# PCB-CCU-IRISCTRL.net
KiCad netlist of a schematic drawn in EAGLE
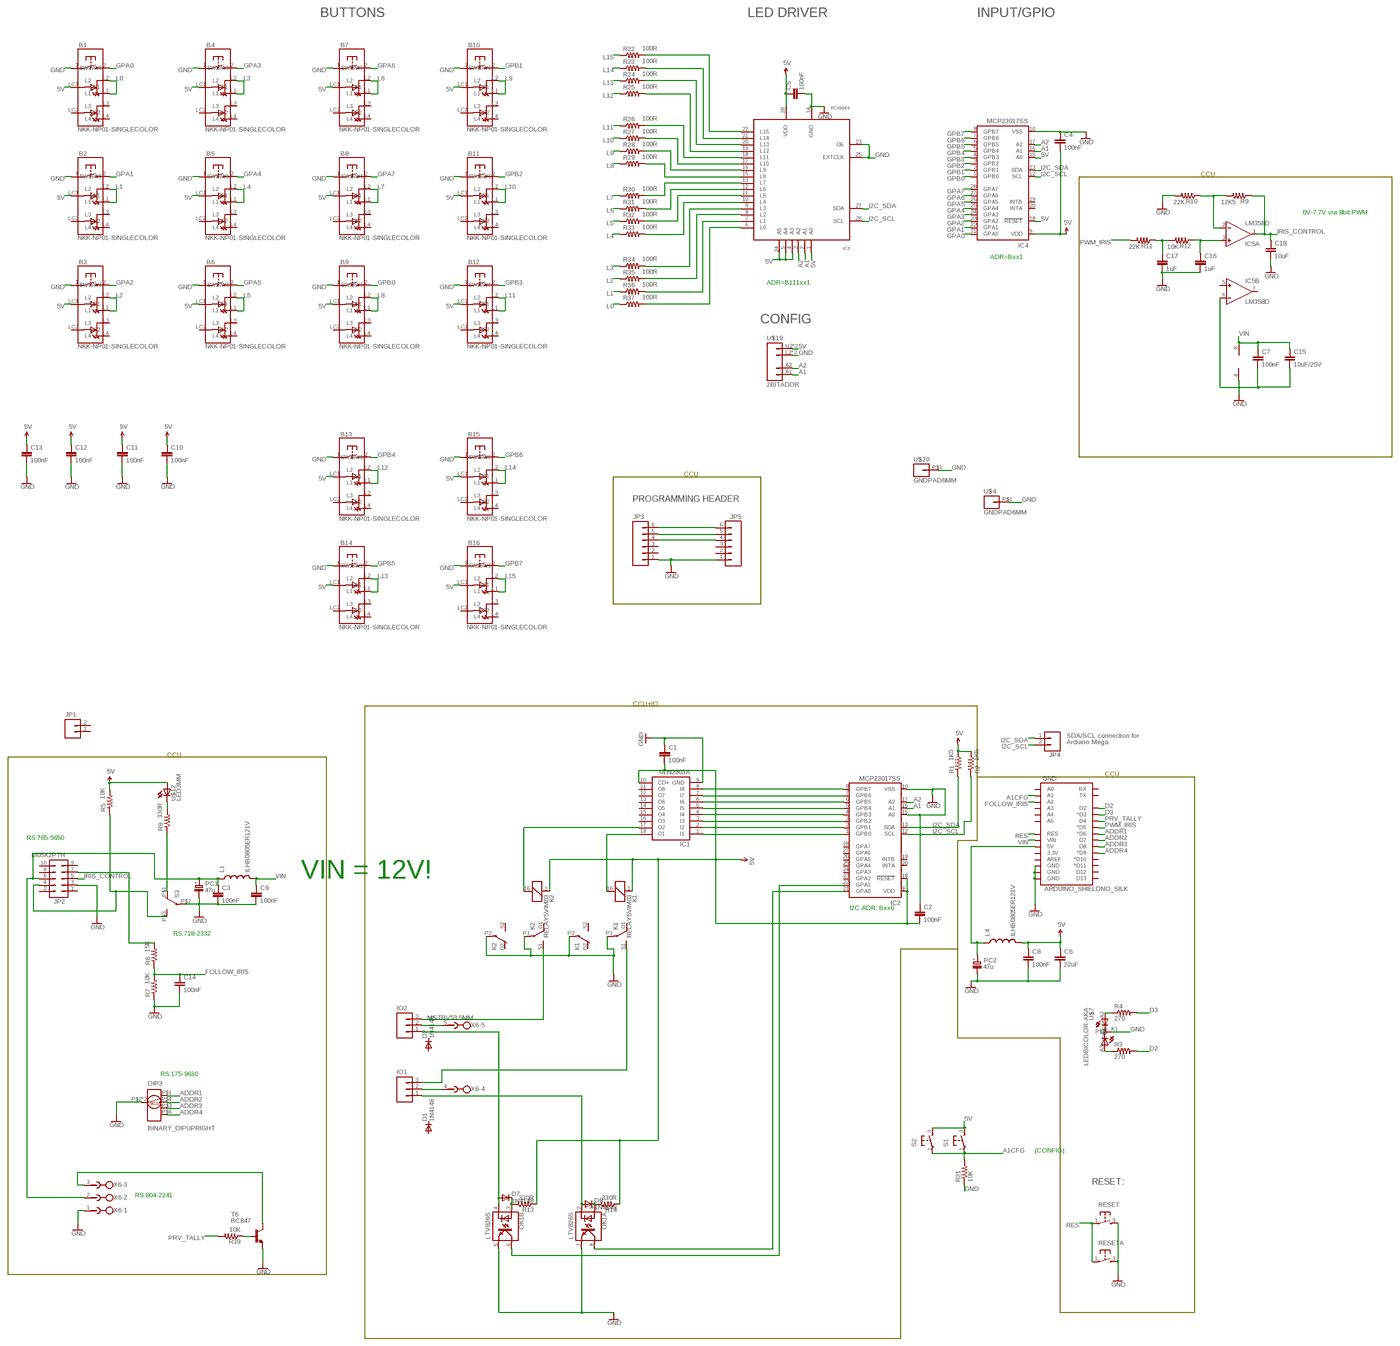
[diagram p0: schematic, sheet 1, overview]
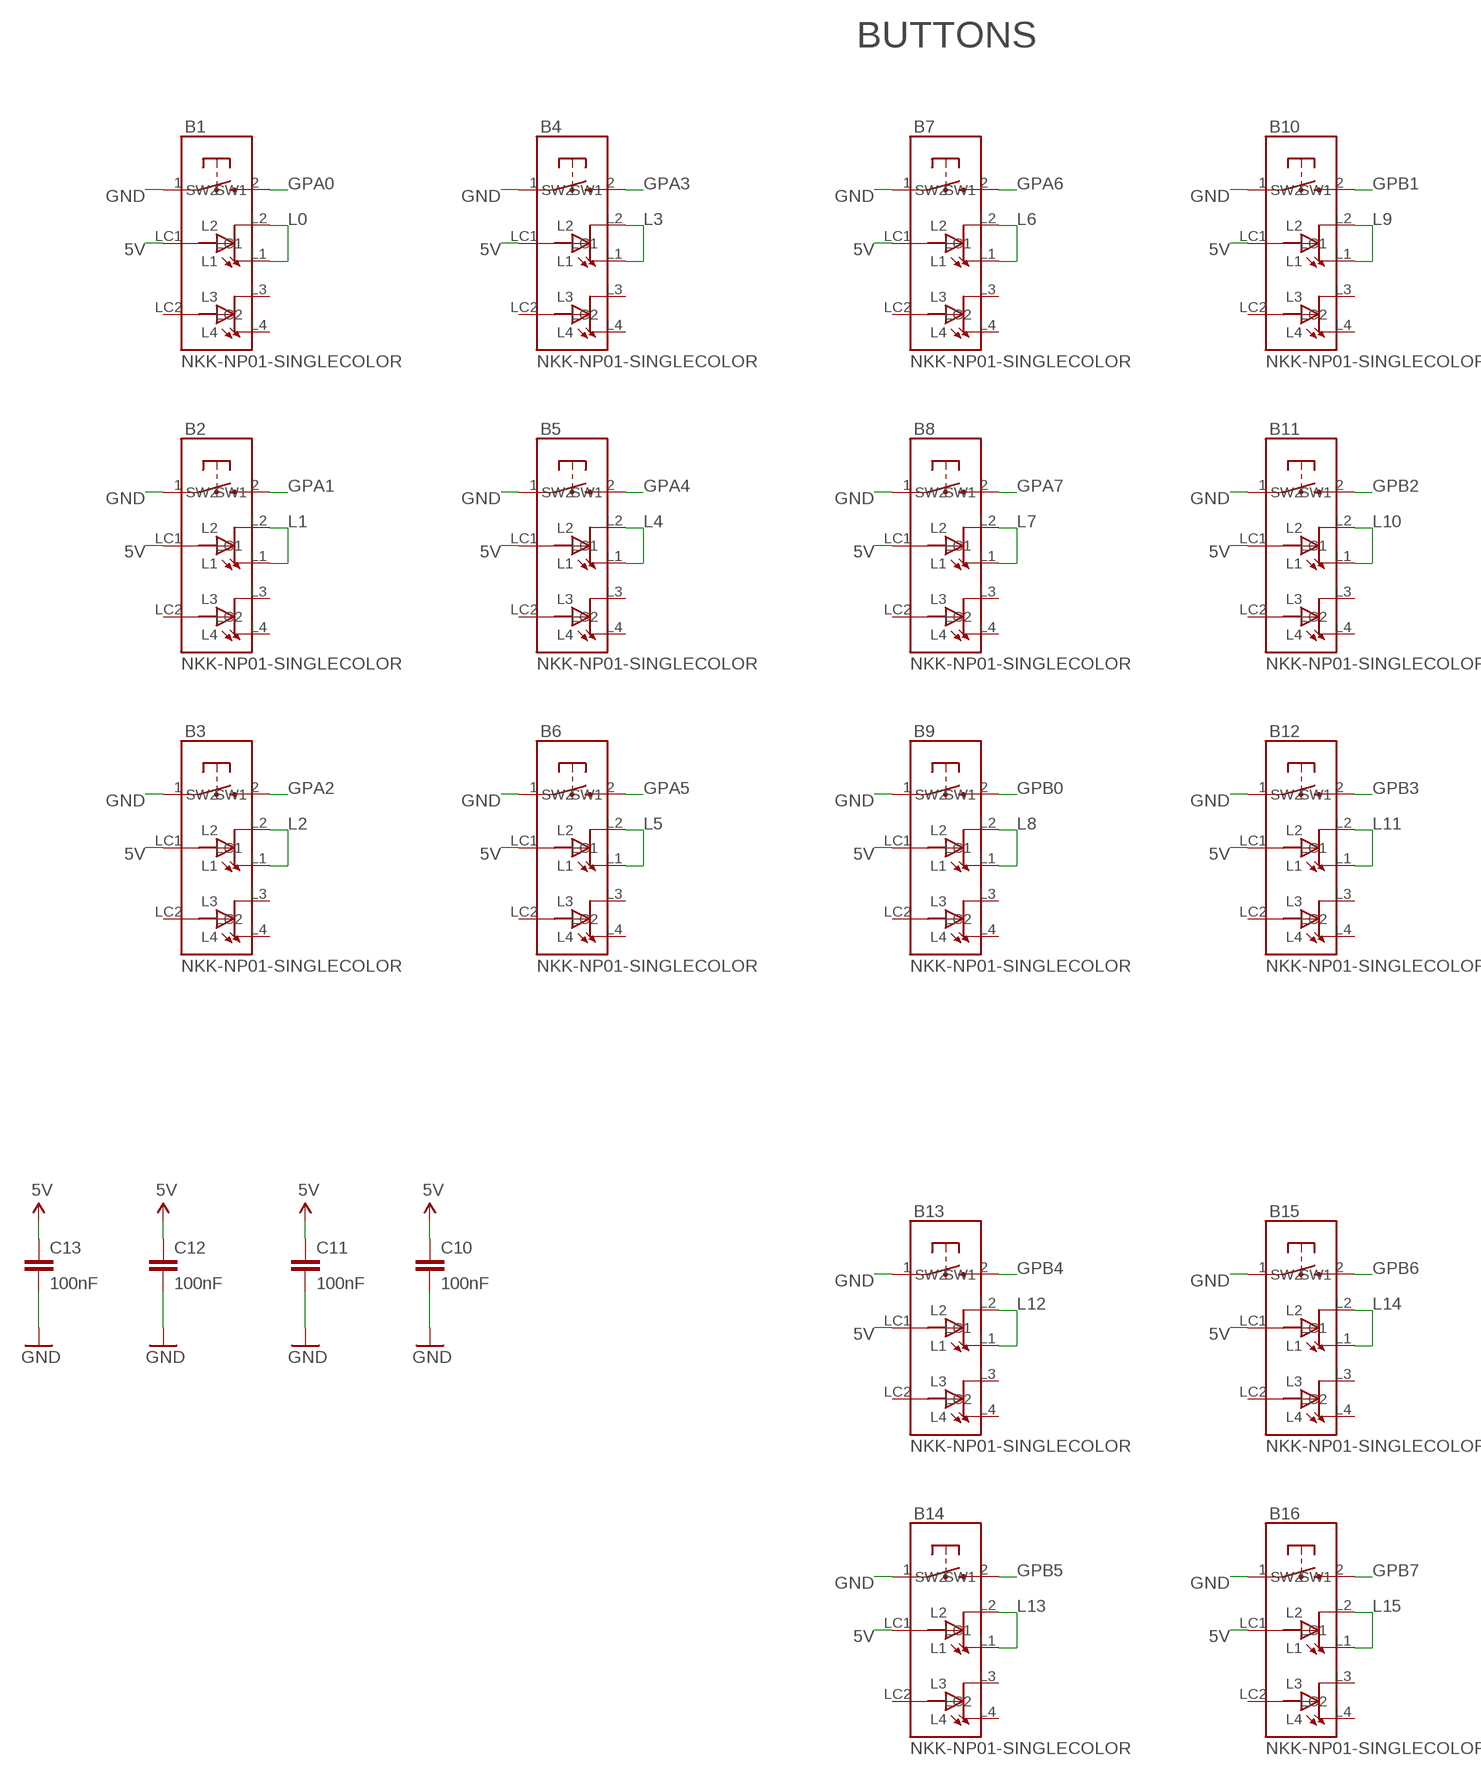
[diagram p1: schematic, sheet 1, part 1 of 4]
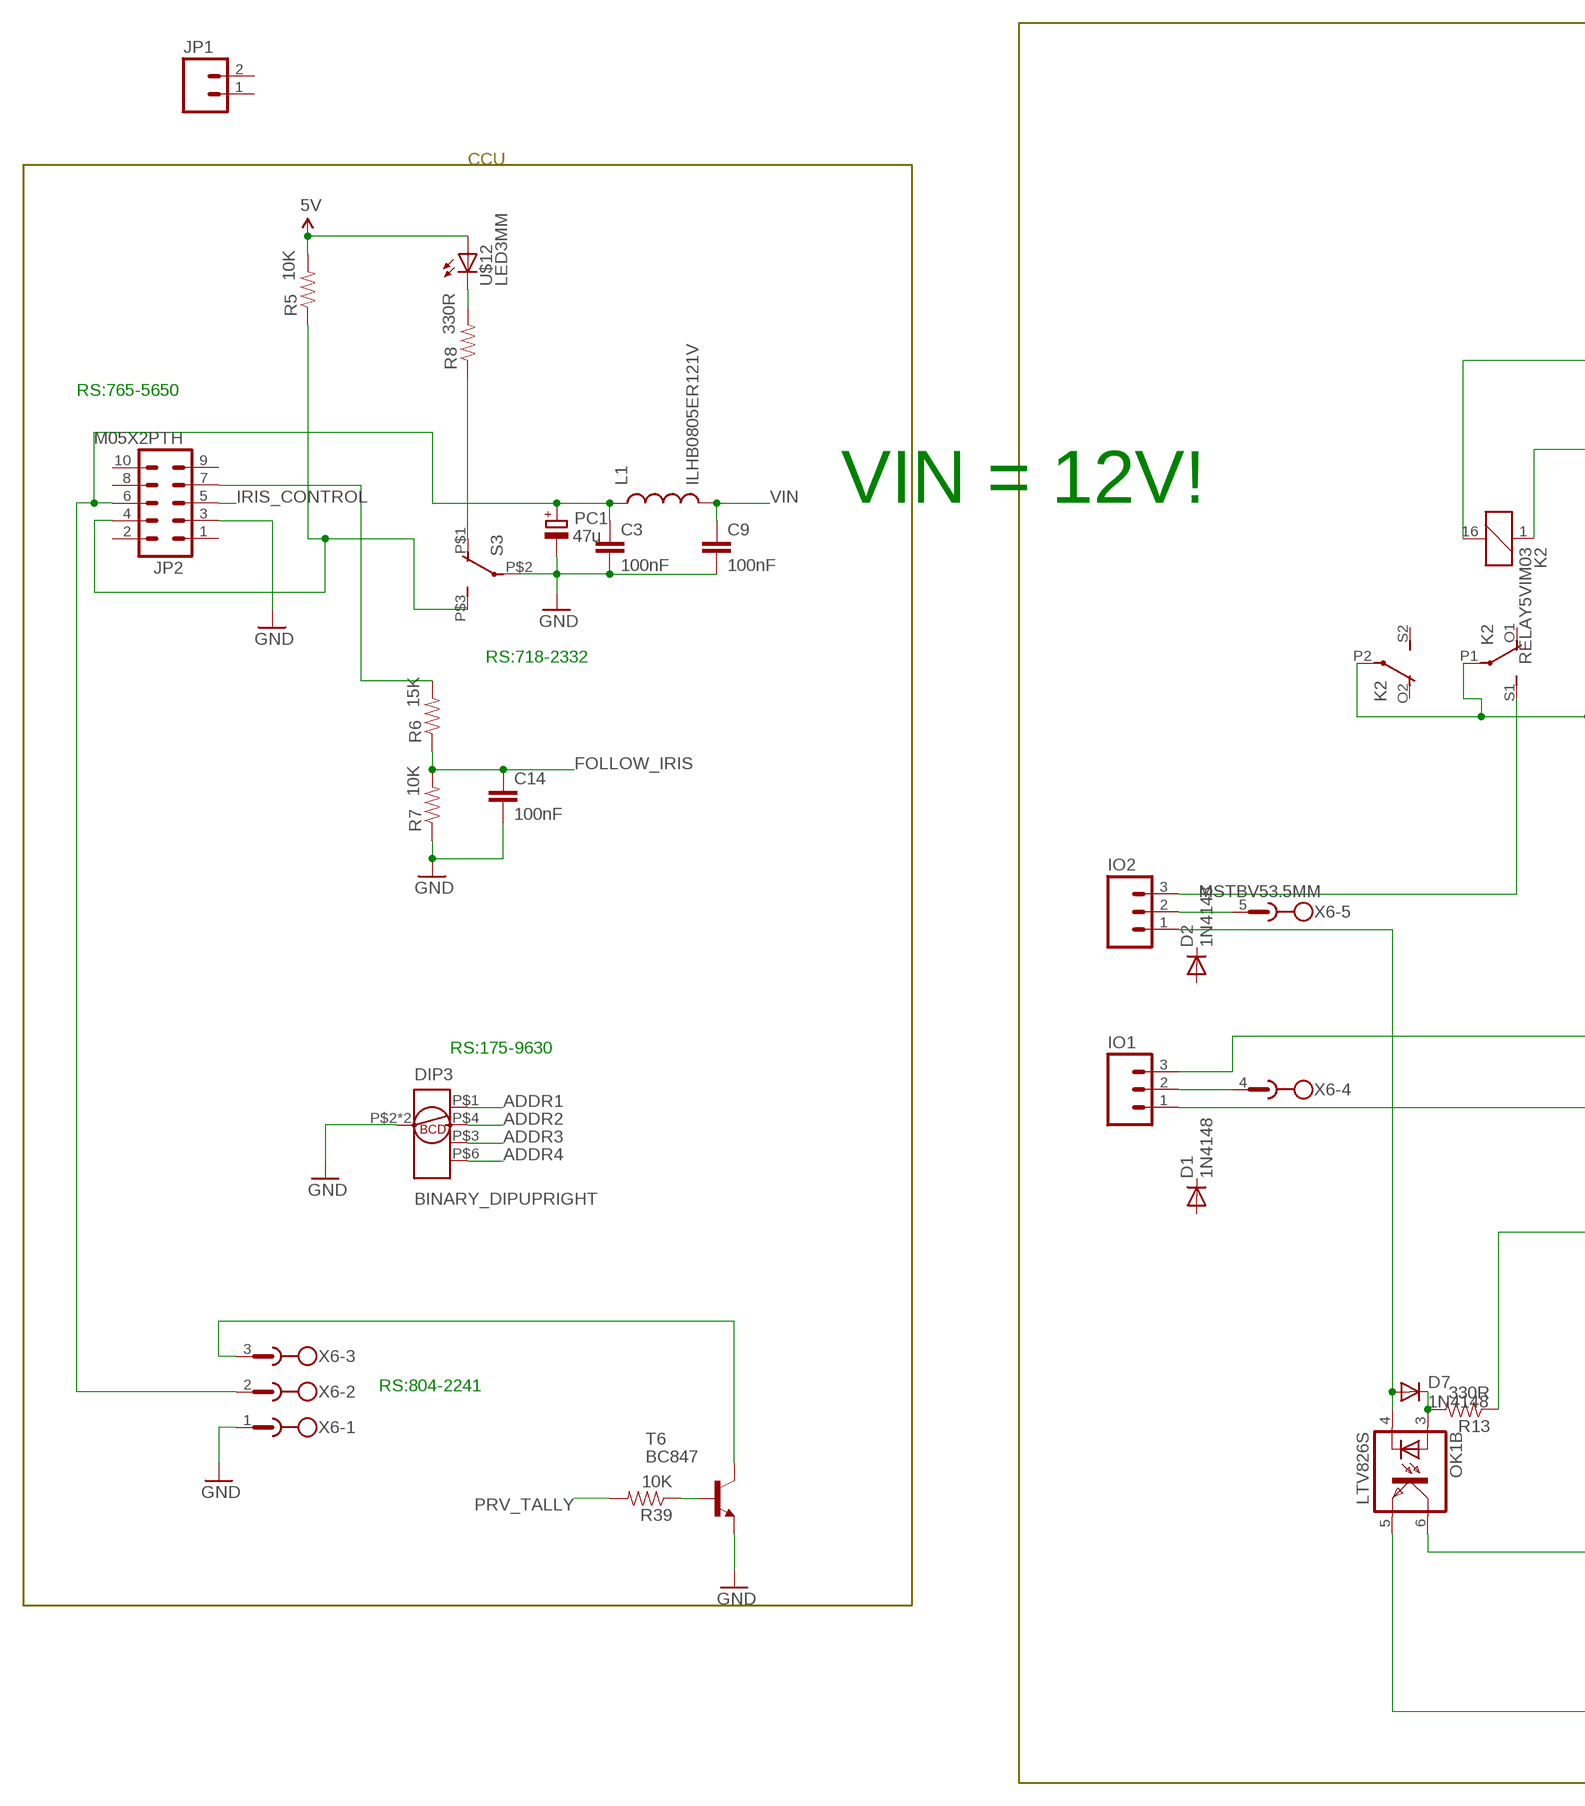
[diagram p2: schematic, sheet 1, part 2 of 4]
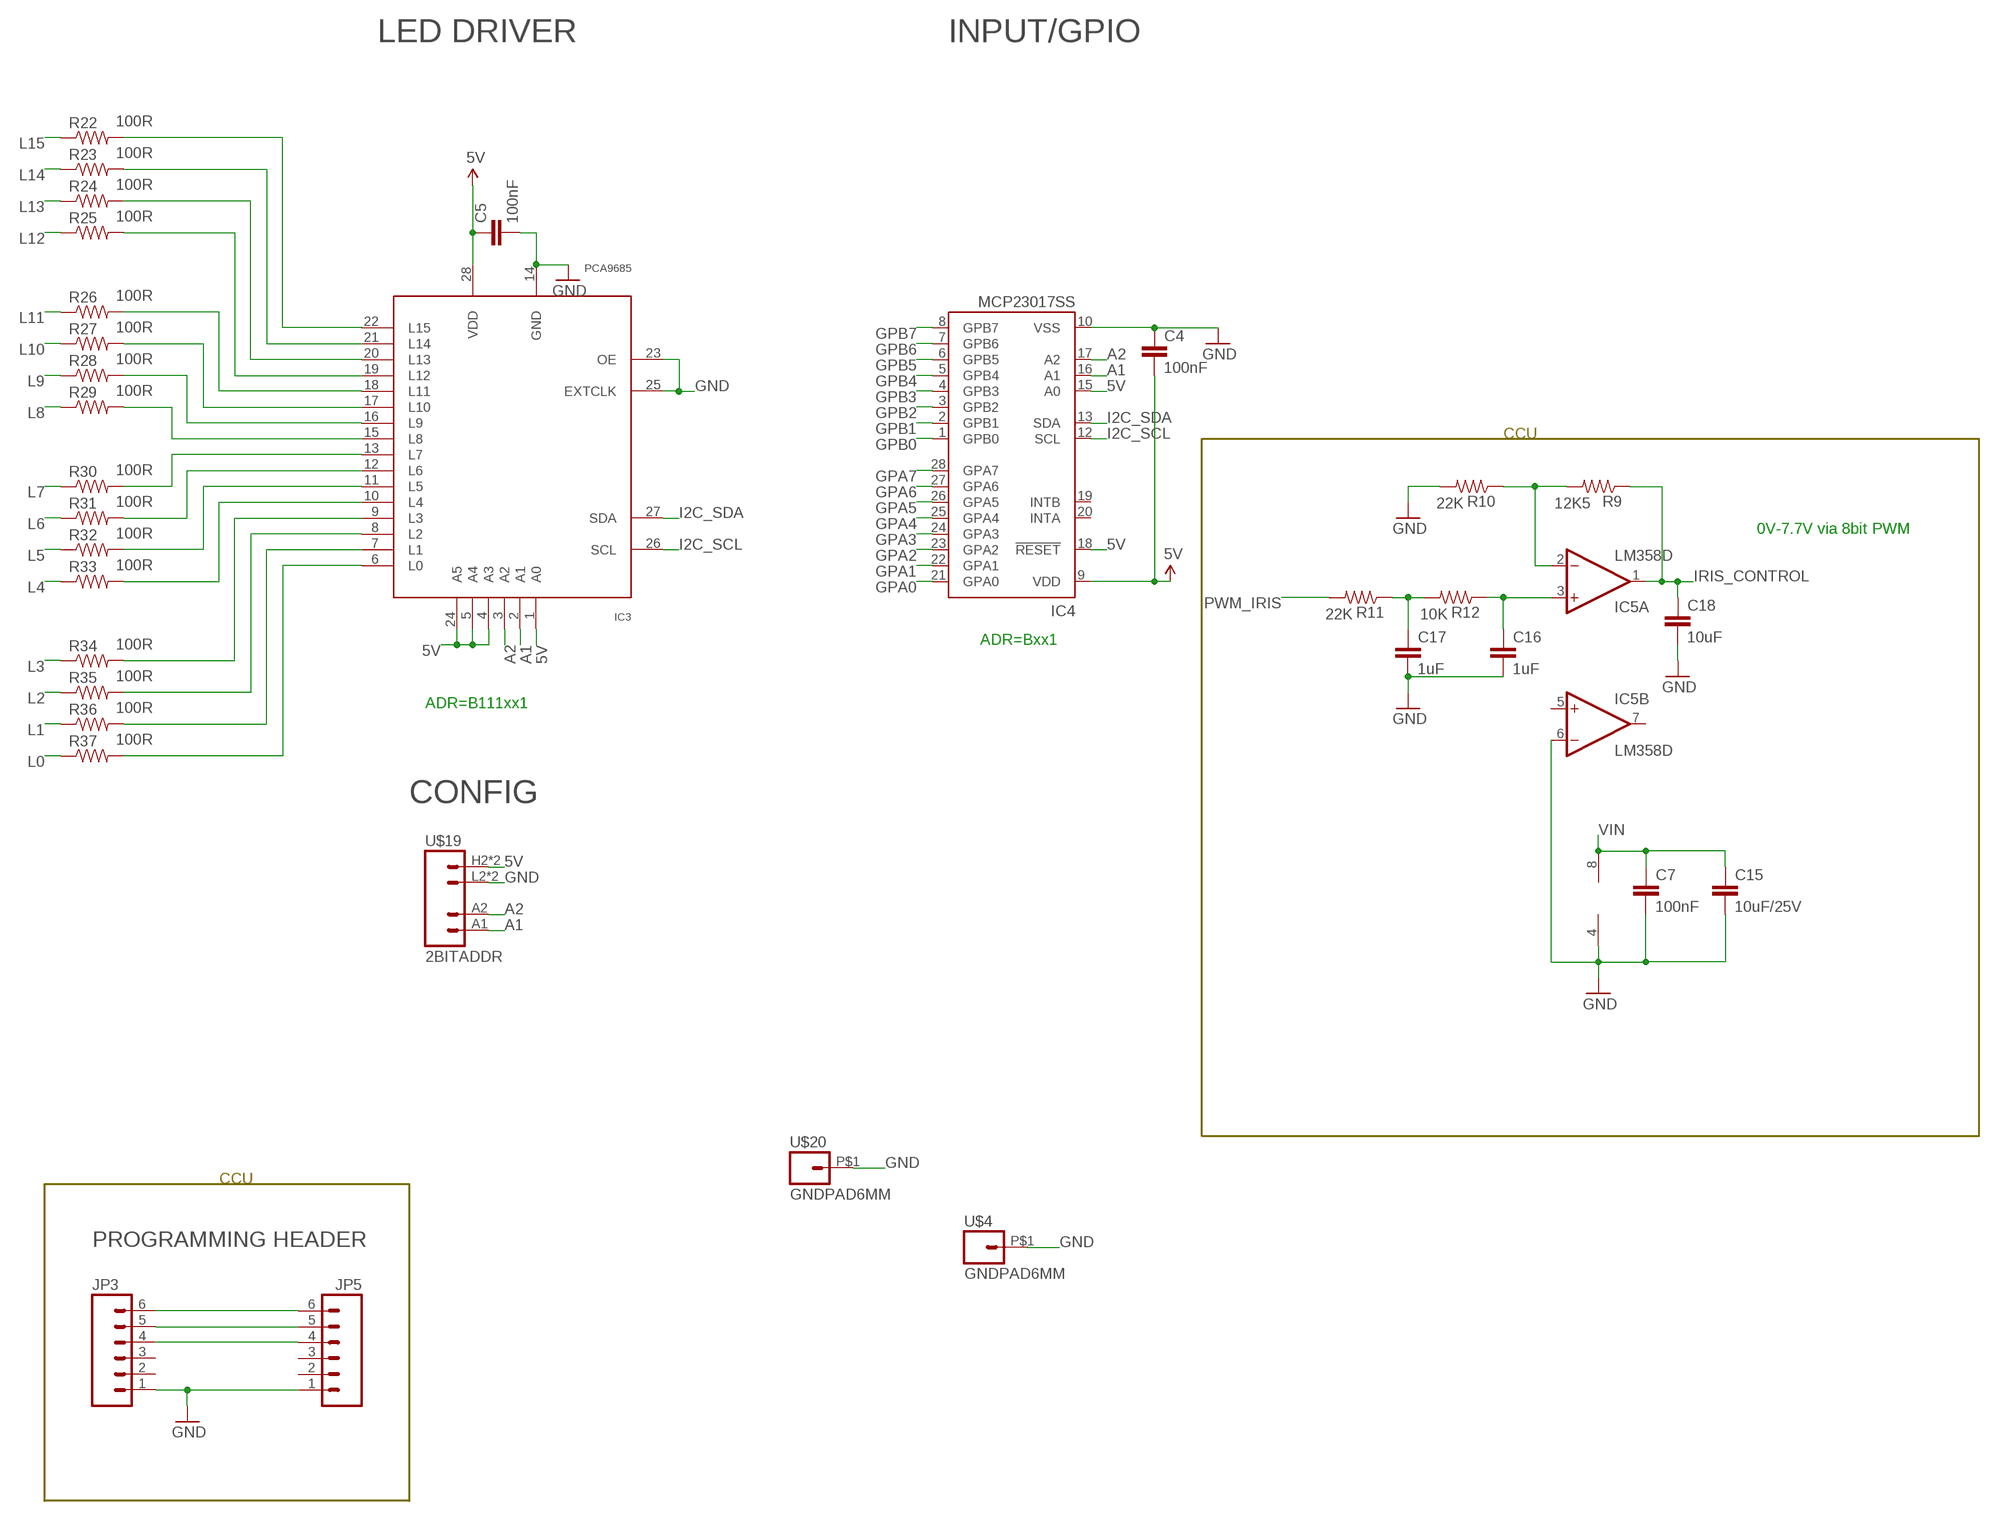
[diagram p3: schematic, sheet 1, part 3 of 4]
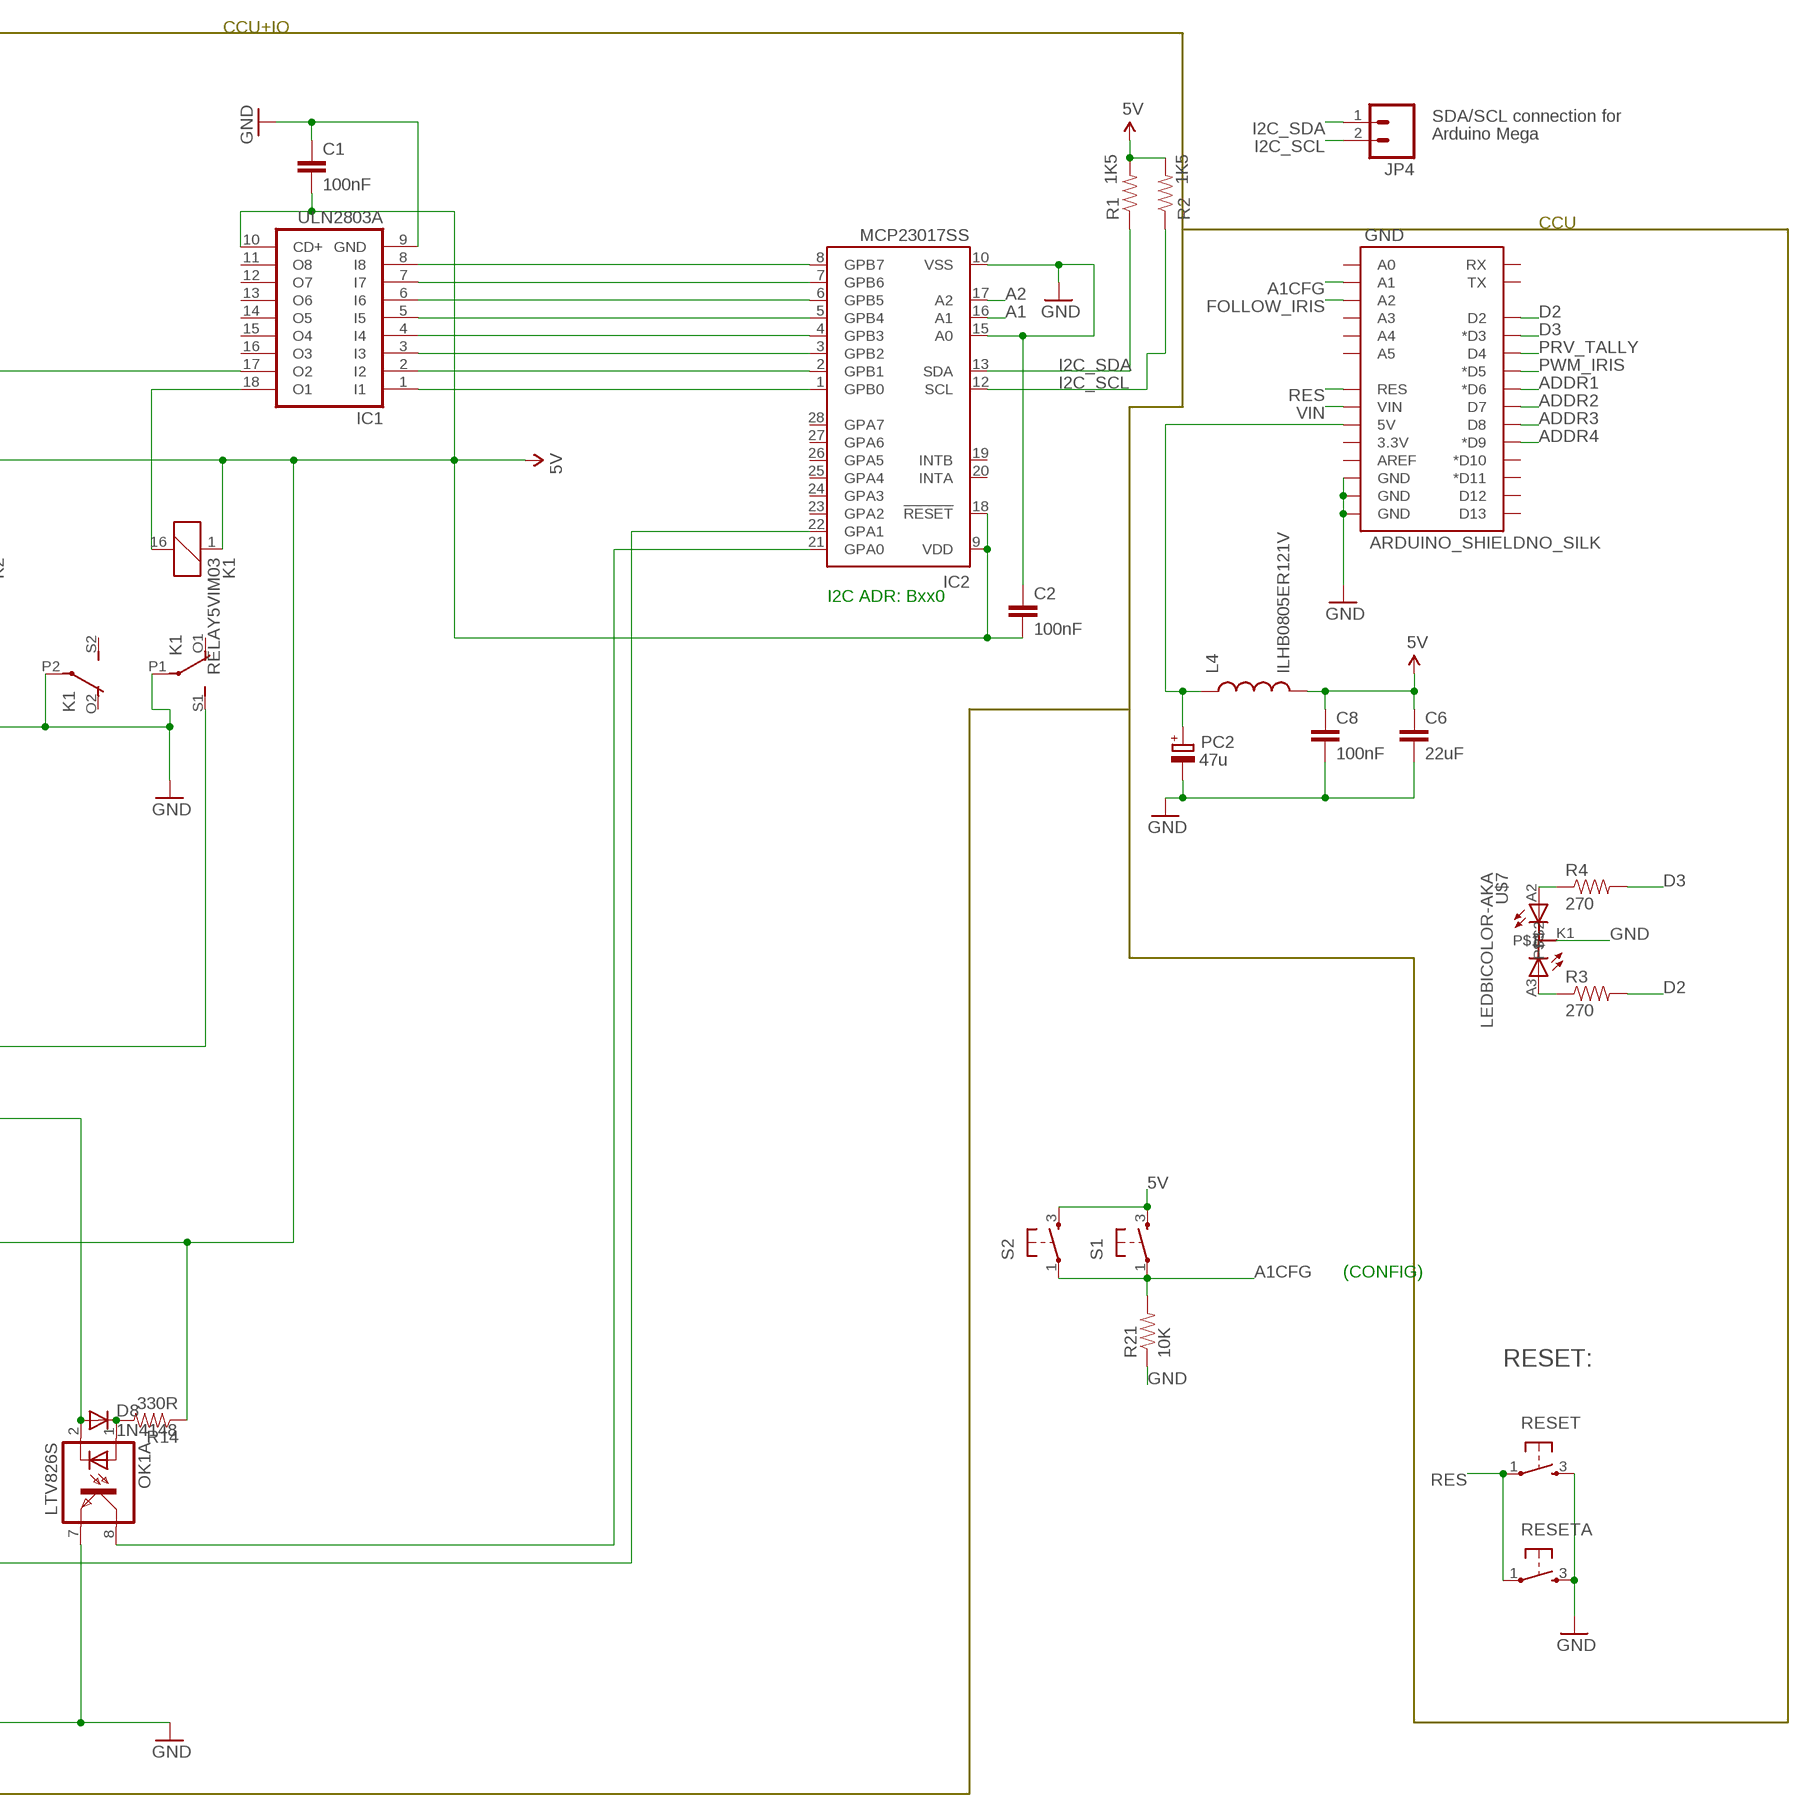
[diagram p4: schematic, sheet 1, part 4 of 4]

(export (version "E")
  (design (tool "Eeschema 10.0.6"))
  (components
    (comp (ref "B1")
      (value "NKK-NP01-SINGLECOLOR")
      (footprint "eagle-import:NKK-NP01")
      (libsource (lib "eagle-import") (part "NKK-NP01-SINGLECOLOR"))
    )
    (comp (ref "B2")
      (value "NKK-NP01-SINGLECOLOR")
      (footprint "eagle-import:NKK-NP01")
      (libsource (lib "eagle-import") (part "NKK-NP01-SINGLECOLOR"))
    )
    (comp (ref "B3")
      (value "NKK-NP01-SINGLECOLOR")
      (footprint "eagle-import:NKK-NP01")
      (libsource (lib "eagle-import") (part "NKK-NP01-SINGLECOLOR"))
    )
    (comp (ref "B4")
      (value "NKK-NP01-SINGLECOLOR")
      (footprint "eagle-import:NKK-NP01")
      (libsource (lib "eagle-import") (part "NKK-NP01-SINGLECOLOR"))
    )
    (comp (ref "B5")
      (value "NKK-NP01-SINGLECOLOR")
      (footprint "eagle-import:NKK-NP01")
      (libsource (lib "eagle-import") (part "NKK-NP01-SINGLECOLOR"))
    )
    (comp (ref "B6")
      (value "NKK-NP01-SINGLECOLOR")
      (footprint "eagle-import:NKK-NP01")
      (libsource (lib "eagle-import") (part "NKK-NP01-SINGLECOLOR"))
    )
    (comp (ref "B7")
      (value "NKK-NP01-SINGLECOLOR")
      (footprint "eagle-import:NKK-NP01")
      (libsource (lib "eagle-import") (part "NKK-NP01-SINGLECOLOR"))
    )
    (comp (ref "B8")
      (value "NKK-NP01-SINGLECOLOR")
      (footprint "eagle-import:NKK-NP01")
      (libsource (lib "eagle-import") (part "NKK-NP01-SINGLECOLOR"))
    )
    (comp (ref "B9")
      (value "NKK-NP01-SINGLECOLOR")
      (footprint "eagle-import:NKK-NP01")
      (libsource (lib "eagle-import") (part "NKK-NP01-SINGLECOLOR"))
    )
    (comp (ref "B10")
      (value "NKK-NP01-SINGLECOLOR")
      (footprint "eagle-import:NKK-NP01")
      (libsource (lib "eagle-import") (part "NKK-NP01-SINGLECOLOR"))
    )
    (comp (ref "B11")
      (value "NKK-NP01-SINGLECOLOR")
      (footprint "eagle-import:NKK-NP01")
      (libsource (lib "eagle-import") (part "NKK-NP01-SINGLECOLOR"))
    )
    (comp (ref "B12")
      (value "NKK-NP01-SINGLECOLOR")
      (footprint "eagle-import:NKK-NP01")
      (libsource (lib "eagle-import") (part "NKK-NP01-SINGLECOLOR"))
    )
    (comp (ref "B13")
      (value "NKK-NP01-SINGLECOLOR")
      (footprint "eagle-import:NKK-NP01")
      (libsource (lib "eagle-import") (part "NKK-NP01-SINGLECOLOR"))
    )
    (comp (ref "B14")
      (value "NKK-NP01-SINGLECOLOR")
      (footprint "eagle-import:NKK-NP01")
      (libsource (lib "eagle-import") (part "NKK-NP01-SINGLECOLOR"))
    )
    (comp (ref "B15")
      (value "NKK-NP01-SINGLECOLOR")
      (footprint "eagle-import:NKK-NP01")
      (libsource (lib "eagle-import") (part "NKK-NP01-SINGLECOLOR"))
    )
    (comp (ref "B16")
      (value "NKK-NP01-SINGLECOLOR")
      (footprint "eagle-import:NKK-NP01")
      (libsource (lib "eagle-import") (part "NKK-NP01-SINGLECOLOR"))
    )
    (comp (ref "C1")
      (value "100nF")
      (footprint "eagle-import:0805")
      (libsource (lib "eagle-import") (part "CAP0805"))
    )
    (comp (ref "C2")
      (value "100nF")
      (footprint "eagle-import:0603-CAP")
      (libsource (lib "eagle-import") (part "CAP0603-CAP"))
    )
    (comp (ref "C3")
      (value "100nF")
      (footprint "eagle-import:0603-CAP")
      (libsource (lib "eagle-import") (part "CAP0603-CAP"))
    )
    (comp (ref "C4")
      (value "100nF")
      (footprint "eagle-import:0603-CAP")
      (libsource (lib "eagle-import") (part "CAP0603-CAP"))
    )
    (comp (ref "C5")
      (value "100nF")
      (footprint "eagle-import:0603-CAP")
      (libsource (lib "eagle-import") (part "CAP0603-CAP"))
    )
    (comp (ref "C6")
      (value "22uF")
      (footprint "eagle-import:0805")
      (libsource (lib "eagle-import") (part "CAP0805"))
    )
    (comp (ref "C7")
      (value "100nF")
      (footprint "eagle-import:0603-CAP")
      (libsource (lib "eagle-import") (part "CAP0603-CAP"))
    )
    (comp (ref "C8")
      (value "100nF")
      (footprint "eagle-import:0603-CAP")
      (libsource (lib "eagle-import") (part "CAP0603-CAP"))
    )
    (comp (ref "C9")
      (value "100nF")
      (footprint "eagle-import:0603-CAP")
      (libsource (lib "eagle-import") (part "CAP0603-CAP"))
    )
    (comp (ref "C10")
      (value "100nF")
      (footprint "eagle-import:0603-CAP")
      (libsource (lib "eagle-import") (part "CAP0603-CAP"))
    )
    (comp (ref "C11")
      (value "100nF")
      (footprint "eagle-import:0603-CAP")
      (libsource (lib "eagle-import") (part "CAP0603-CAP"))
    )
    (comp (ref "C12")
      (value "100nF")
      (footprint "eagle-import:0603-CAP")
      (libsource (lib "eagle-import") (part "CAP0603-CAP"))
    )
    (comp (ref "C13")
      (value "100nF")
      (footprint "eagle-import:0603-CAP")
      (libsource (lib "eagle-import") (part "CAP0603-CAP"))
    )
    (comp (ref "C14")
      (value "100nF")
      (footprint "eagle-import:0603-CAP")
      (libsource (lib "eagle-import") (part "CAP0603-CAP"))
    )
    (comp (ref "C15")
      (value "10uF/25V")
      (footprint "eagle-import:0805")
      (libsource (lib "eagle-import") (part "CAP0805"))
    )
    (comp (ref "C16")
      (value "1uF")
      (footprint "eagle-import:0805")
      (libsource (lib "eagle-import") (part "CAP0805"))
    )
    (comp (ref "C17")
      (value "1uF")
      (footprint "eagle-import:0805")
      (libsource (lib "eagle-import") (part "CAP0805"))
    )
    (comp (ref "C18")
      (value "10uF")
      (footprint "eagle-import:0805")
      (libsource (lib "eagle-import") (part "CAP0805"))
    )
    (comp (ref "D1")
      (value "1N4148")
      (footprint "eagle-import:SOD-323")
      (libsource (lib "eagle-import") (part "DIODESOD"))
    )
    (comp (ref "D2")
      (value "1N4148")
      (footprint "eagle-import:SOD-323")
      (libsource (lib "eagle-import") (part "DIODESOD"))
    )
    (comp (ref "D7")
      (value "1N4148")
      (footprint "eagle-import:SOD-323")
      (libsource (lib "eagle-import") (part "DIODESOD"))
    )
    (comp (ref "D8")
      (value "1N4148")
      (footprint "eagle-import:SOD-323")
      (libsource (lib "eagle-import") (part "DIODESOD"))
    )
    (comp (ref "DIP3")
      (value "BINARY_DIPUPRIGHT")
      (footprint "eagle-import:P65SMT_UPRIGHT_TH")
      (libsource (lib "eagle-import") (part "BINARY_DIPUPRIGHT"))
    )
    (comp (ref "GND")
      (value "ARDUINO_SHIELDNO_SILK")
      (footprint "eagle-import:DUEMILANOVE_VIAS")
      (libsource (lib "eagle-import") (part "ARDUINO_SHIELDNO_SILK"))
    )
    (comp (ref "IC1")
      (value "ULN2803A")
      (footprint "eagle-import:SO18W")
      (libsource (lib "eagle-import") (part "ULN2803ASO18W"))
    )
    (comp (ref "IC2")
      (value "MCP23017SS")
      (footprint "eagle-import:SSOP28")
      (fields (field (name "MF") "MICROCHIP") (field (name "MPN") "MCP23017-E/SS"))
      (libsource (lib "eagle-import") (part "MCP23017SS"))
    )
    (comp (ref "IC3")
      (value "PCA9685")
      (footprint "eagle-import:TSSOP28")
      (libsource (lib "eagle-import") (part "PCA9685"))
    )
    (comp (ref "IC4")
      (value "MCP23017SS")
      (footprint "eagle-import:SSOP28")
      (fields
        (field (name "MF") "MICROCHIP")
        (field (name "MPN") "MCP23017-E/SS")
        (field (name "MPN_1") "MCP23017-E/SS")
        (field (name "OC_FARNELL") "1467674")
        (field (name "OC_NEWARK") "31K2960")
      )
      (libsource (lib "eagle-import") (part "MCP23017SS"))
    )
    (comp (ref "IC5")
      (value "LM358D")
      (footprint "eagle-import:SO08")
      (libsource (lib "eagle-import") (part "LM358D"))
    )
    (comp (ref "IO1")
      (value "M03LOCK")
      (footprint "eagle-import:1X03_LOCK")
      (libsource (lib "eagle-import") (part "M03LOCK"))
    )
    (comp (ref "IO2")
      (value "M03LOCK")
      (footprint "eagle-import:1X03_LOCK")
      (libsource (lib "eagle-import") (part "M03LOCK"))
    )
    (comp (ref "JP1")
      (value "M02PTH")
      (footprint "eagle-import:1X02")
      (libsource (lib "eagle-import") (part "M02PTH"))
    )
    (comp (ref "JP2")
      (value "M05X2PTH")
      (footprint "eagle-import:AVR_ICSP")
      (libsource (lib "eagle-import") (part "M05X2PTH"))
    )
    (comp (ref "JP3")
      (value "M06POLAR")
      (footprint "eagle-import:MOLEX-1X6")
      (libsource (lib "eagle-import") (part "M06POLAR"))
    )
    (comp (ref "JP4")
      (value "M02PTH")
      (footprint "eagle-import:1X02")
      (libsource (lib "eagle-import") (part "M02PTH"))
    )
    (comp (ref "JP5")
      (value "M06POLAR")
      (footprint "eagle-import:MOLEX-1X6")
      (libsource (lib "eagle-import") (part "M06POLAR"))
    )
    (comp (ref "K1")
      (value "RELAY5VIM03")
      (footprint "eagle-import:DS2Y")
      (libsource (lib "eagle-import") (part "RELAY5VIM03"))
    )
    (comp (ref "K2")
      (value "RELAY5VIM03")
      (footprint "eagle-import:DS2Y")
      (libsource (lib "eagle-import") (part "RELAY5VIM03"))
    )
    (comp (ref "L1")
      (value "ILHB0805ER121V")
      (footprint "eagle-import:0805")
      (libsource (lib "eagle-import") (part "INDUCTOR0805"))
    )
    (comp (ref "L4")
      (value "ILHB0805ER121V")
      (footprint "eagle-import:0805")
      (libsource (lib "eagle-import") (part "INDUCTOR0805"))
    )
    (comp (ref "OK1")
      (value "LTV826S")
      (footprint "eagle-import:DIL8-SMD")
      (libsource (lib "eagle-import") (part "LTV826S"))
    )
    (comp (ref "PC1")
      (value "47u")
      (footprint "eagle-import:PANASONIC_D")
      (libsource (lib "eagle-import") (part "CPOL-EUD"))
    )
    (comp (ref "PC2")
      (value "47u")
      (footprint "eagle-import:PANASONIC_D")
      (libsource (lib "eagle-import") (part "CPOL-EUD"))
    )
    (comp (ref "R1")
      (value "1K5")
      (footprint "eagle-import:0603-RES")
      (libsource (lib "eagle-import") (part "RESISTOR0603-RES"))
    )
    (comp (ref "R2")
      (value "1K5")
      (footprint "eagle-import:0603-RES")
      (libsource (lib "eagle-import") (part "RESISTOR0603-RES"))
    )
    (comp (ref "R3")
      (value "270")
      (footprint "eagle-import:0603-RES")
      (libsource (lib "eagle-import") (part "RESISTOR0603-RES"))
    )
    (comp (ref "R4")
      (value "270")
      (footprint "eagle-import:0603-RES")
      (libsource (lib "eagle-import") (part "RESISTOR0603-RES"))
    )
    (comp (ref "R5")
      (value "10K")
      (footprint "eagle-import:0603-RES")
      (libsource (lib "eagle-import") (part "RESISTOR0603-RES"))
    )
    (comp (ref "R6")
      (value "15K")
      (footprint "eagle-import:0603-RES")
      (libsource (lib "eagle-import") (part "RESISTOR0603-RES"))
    )
    (comp (ref "R7")
      (value "10K")
      (footprint "eagle-import:0603-RES")
      (libsource (lib "eagle-import") (part "RESISTOR0603-RES"))
    )
    (comp (ref "R8")
      (value "330R")
      (footprint "eagle-import:0603-RES")
      (libsource (lib "eagle-import") (part "RESISTOR0603-RES"))
    )
    (comp (ref "R9")
      (value "12K5")
      (footprint "eagle-import:0603-RES")
      (libsource (lib "eagle-import") (part "RESISTOR0603-RES"))
    )
    (comp (ref "R10")
      (value "22K")
      (footprint "eagle-import:0603-RES")
      (libsource (lib "eagle-import") (part "RESISTOR0603-RES"))
    )
    (comp (ref "R11")
      (value "22K")
      (footprint "eagle-import:0603-RES")
      (libsource (lib "eagle-import") (part "RESISTOR0603-RES"))
    )
    (comp (ref "R12")
      (value "10K")
      (footprint "eagle-import:0603-RES")
      (libsource (lib "eagle-import") (part "RESISTOR0603-RES"))
    )
    (comp (ref "R13")
      (value "330R")
      (footprint "eagle-import:0603-RES")
      (libsource (lib "eagle-import") (part "RESISTOR0603-RES"))
    )
    (comp (ref "R14")
      (value "330R")
      (footprint "eagle-import:0603-RES")
      (libsource (lib "eagle-import") (part "RESISTOR0603-RES"))
    )
    (comp (ref "R21")
      (value "10K")
      (footprint "eagle-import:0603-RES")
      (libsource (lib "eagle-import") (part "RESISTOR0603-RES"))
    )
    (comp (ref "R22")
      (value "100R")
      (footprint "eagle-import:0603-RES")
      (libsource (lib "eagle-import") (part "RESISTOR0603-RES"))
    )
    (comp (ref "R23")
      (value "100R")
      (footprint "eagle-import:0603-RES")
      (libsource (lib "eagle-import") (part "RESISTOR0603-RES"))
    )
    (comp (ref "R24")
      (value "100R")
      (footprint "eagle-import:0603-RES")
      (libsource (lib "eagle-import") (part "RESISTOR0603-RES"))
    )
    (comp (ref "R25")
      (value "100R")
      (footprint "eagle-import:0603-RES")
      (libsource (lib "eagle-import") (part "RESISTOR0603-RES"))
    )
    (comp (ref "R26")
      (value "100R")
      (footprint "eagle-import:0603-RES")
      (libsource (lib "eagle-import") (part "RESISTOR0603-RES"))
    )
    (comp (ref "R27")
      (value "100R")
      (footprint "eagle-import:0603-RES")
      (libsource (lib "eagle-import") (part "RESISTOR0603-RES"))
    )
    (comp (ref "R28")
      (value "100R")
      (footprint "eagle-import:0603-RES")
      (libsource (lib "eagle-import") (part "RESISTOR0603-RES"))
    )
    (comp (ref "R29")
      (value "100R")
      (footprint "eagle-import:0603-RES")
      (libsource (lib "eagle-import") (part "RESISTOR0603-RES"))
    )
    (comp (ref "R30")
      (value "100R")
      (footprint "eagle-import:0603-RES")
      (libsource (lib "eagle-import") (part "RESISTOR0603-RES"))
    )
    (comp (ref "R31")
      (value "100R")
      (footprint "eagle-import:0603-RES")
      (libsource (lib "eagle-import") (part "RESISTOR0603-RES"))
    )
    (comp (ref "R32")
      (value "100R")
      (footprint "eagle-import:0603-RES")
      (libsource (lib "eagle-import") (part "RESISTOR0603-RES"))
    )
    (comp (ref "R33")
      (value "100R")
      (footprint "eagle-import:0603-RES")
      (libsource (lib "eagle-import") (part "RESISTOR0603-RES"))
    )
    (comp (ref "R34")
      (value "100R")
      (footprint "eagle-import:0603-RES")
      (libsource (lib "eagle-import") (part "RESISTOR0603-RES"))
    )
    (comp (ref "R35")
      (value "100R")
      (footprint "eagle-import:0603-RES")
      (libsource (lib "eagle-import") (part "RESISTOR0603-RES"))
    )
    (comp (ref "R36")
      (value "100R")
      (footprint "eagle-import:0603-RES")
      (libsource (lib "eagle-import") (part "RESISTOR0603-RES"))
    )
    (comp (ref "R37")
      (value "100R")
      (footprint "eagle-import:0603-RES")
      (libsource (lib "eagle-import") (part "RESISTOR0603-RES"))
    )
    (comp (ref "R39")
      (value "10K")
      (footprint "eagle-import:0603-RES")
      (libsource (lib "eagle-import") (part "RESISTOR0603-RES"))
    )
    (comp (ref "RESET")
      (value "TAC_SWITCH")
      (footprint "eagle-import:PUSHBUTTON")
      (libsource (lib "eagle-import") (part "TAC_SWITCH"))
    )
    (comp (ref "RESETA")
      (value "TAC_SWITCH")
      (footprint "eagle-import:PUSHBUTTON")
      (libsource (lib "eagle-import") (part "TAC_SWITCH"))
    )
    (comp (ref "S1")
      (value "TAC_SWITCH")
      (footprint "eagle-import:PUSHBUTTON")
      (libsource (lib "eagle-import") (part "TAC_SWITCH"))
    )
    (comp (ref "S2")
      (value "TAC_SWITCH")
      (footprint "eagle-import:PUSHBUTTON")
      (libsource (lib "eagle-import") (part "TAC_SWITCH"))
    )
    (comp (ref "S3")
      (value "SWITCH-DPST")
      (footprint "eagle-import:TECONNECTIVITY-DPST")
      (libsource (lib "eagle-import") (part "SWITCH-DPST"))
    )
    (comp (ref "T6")
      (value "BC847")
      (footprint "eagle-import:SOT23")
      (libsource (lib "eagle-import") (part "BC847"))
    )
    (comp (ref "U$4")
      (value "GNDPAD6MM")
      (footprint "eagle-import:3.2MMPAD6MM")
      (libsource (lib "eagle-import") (part "GNDPAD6MM"))
    )
    (comp (ref "U$7")
      (value "LEDBICOLOR-AKA")
      (footprint "eagle-import:LED5MM-BICOLOR")
      (libsource (lib "eagle-import") (part "LEDBICOLOR-AKA"))
    )
    (comp (ref "U$12")
      (value "LED3MM")
      (footprint "eagle-import:LED3MM")
      (libsource (lib "eagle-import") (part "LED3MM"))
    )
    (comp (ref "U$19")
      (value "2BITADDR")
      (footprint "eagle-import:2BITADDR")
      (libsource (lib "eagle-import") (part "2BITADDR"))
    )
    (comp (ref "U$20")
      (value "GNDPAD6MM")
      (footprint "eagle-import:3.2MMPAD6MM")
      (libsource (lib "eagle-import") (part "GNDPAD6MM"))
    )
    (comp (ref "X6")
      (value "MSTBV53.5MM")
      (footprint "eagle-import:MSTBV5-3.5")
      (libsource (lib "eagle-import") (part "MSTBV53.5MM"))
    )
  )
  (nets
    (net (code "1") (name "5V") (class "Default")
      (node (ref "B1") (pin "LC1") (pinfunction "LC1_LC1") (pintype "bidirectional"))
      (node (ref "B10") (pin "LC1") (pinfunction "LC1_LC1") (pintype "bidirectional"))
      (node (ref "B11") (pin "LC1") (pinfunction "LC1_LC1") (pintype "bidirectional"))
      (node (ref "B12") (pin "LC1") (pinfunction "LC1_LC1") (pintype "bidirectional"))
      (node (ref "B13") (pin "LC1") (pinfunction "LC1_LC1") (pintype "bidirectional"))
      (node (ref "B14") (pin "LC1") (pinfunction "LC1_LC1") (pintype "bidirectional"))
      (node (ref "B15") (pin "LC1") (pinfunction "LC1_LC1") (pintype "bidirectional"))
      (node (ref "B16") (pin "LC1") (pinfunction "LC1_LC1") (pintype "bidirectional"))
      (node (ref "B2") (pin "LC1") (pinfunction "LC1_LC1") (pintype "bidirectional"))
      (node (ref "B3") (pin "LC1") (pinfunction "LC1_LC1") (pintype "bidirectional"))
      (node (ref "B4") (pin "LC1") (pinfunction "LC1_LC1") (pintype "bidirectional"))
      (node (ref "B5") (pin "LC1") (pinfunction "LC1_LC1") (pintype "bidirectional"))
      (node (ref "B6") (pin "LC1") (pinfunction "LC1_LC1") (pintype "bidirectional"))
      (node (ref "B7") (pin "LC1") (pinfunction "LC1_LC1") (pintype "bidirectional"))
      (node (ref "B8") (pin "LC1") (pinfunction "LC1_LC1") (pintype "bidirectional"))
      (node (ref "B9") (pin "LC1") (pinfunction "LC1_LC1") (pintype "bidirectional"))
      (node (ref "C1") (pin "2") (pinfunction "2_2") (pintype "passive"))
      (node (ref "C10") (pin "1") (pinfunction "1_1") (pintype "passive"))
      (node (ref "C11") (pin "1") (pinfunction "1_1") (pintype "passive"))
      (node (ref "C12") (pin "1") (pinfunction "1_1") (pintype "passive"))
      (node (ref "C13") (pin "1") (pinfunction "1_1") (pintype "passive"))
      (node (ref "C2") (pin "2") (pinfunction "2_2") (pintype "passive"))
      (node (ref "C4") (pin "2") (pinfunction "2_2") (pintype "passive"))
      (node (ref "C5") (pin "1") (pinfunction "1_1") (pintype "passive"))
      (node (ref "C6") (pin "1") (pinfunction "1_1") (pintype "passive"))
      (node (ref "C8") (pin "1") (pinfunction "1_1") (pintype "passive"))
      (node (ref "IC1") (pin "10") (pinfunction "CD+_10") (pintype "passive"))
      (node (ref "IC2") (pin "18") (pinfunction "~{RESET}_18") (pintype "input"))
      (node (ref "IC2") (pin "9") (pinfunction "VDD_9") (pintype "power_in"))
      (node (ref "IC3") (pin "1") (pinfunction "A0_1") (pintype "input"))
      (node (ref "IC3") (pin "24") (pinfunction "A5_24") (pintype "input"))
      (node (ref "IC3") (pin "28") (pinfunction "VDD_28") (pintype "power_in"))
      (node (ref "IC3") (pin "4") (pinfunction "A3_4") (pintype "input"))
      (node (ref "IC3") (pin "5") (pinfunction "A4_5") (pintype "input"))
      (node (ref "IC4") (pin "15") (pinfunction "A0_15") (pintype "input"))
      (node (ref "IC4") (pin "18") (pinfunction "~{RESET}_18") (pintype "input"))
      (node (ref "IC4") (pin "9") (pinfunction "VDD_9") (pintype "power_in"))
      (node (ref "K1") (pin "1") (pinfunction "1_1") (pintype "passive"))
      (node (ref "K2") (pin "1") (pinfunction "1_1") (pintype "passive"))
      (node (ref "L4") (pin "2") (pinfunction "2_2") (pintype "passive"))
      (node (ref "R1") (pin "2") (pinfunction "2_2") (pintype "passive"))
      (node (ref "R13") (pin "1") (pinfunction "1_1") (pintype "passive"))
      (node (ref "R14") (pin "1") (pinfunction "1_1") (pintype "passive"))
      (node (ref "R2") (pin "2") (pinfunction "2_2") (pintype "passive"))
      (node (ref "R5") (pin "2") (pinfunction "2_2") (pintype "passive"))
      (node (ref "S1") (pin "3") (pinfunction "3_3") (pintype "passive"))
      (node (ref "S2") (pin "3") (pinfunction "3_3") (pintype "passive"))
      (node (ref "U$12") (pin "A") (pinfunction "A_A") (pintype "passive"))
      (node (ref "U$19") (pin "H2") (pinfunction "VCC_H2") (pintype "passive"))
      (node (ref "U$19") (pin "H3") (pinfunction "VCC_H3") (pintype "passive"))
    )
    (net (code "2") (name "A1") (class "Default")
      (node (ref "IC2") (pin "16") (pinfunction "A1_16") (pintype "input"))
      (node (ref "IC3") (pin "2") (pinfunction "A1_2") (pintype "input"))
      (node (ref "IC4") (pin "16") (pinfunction "A1_16") (pintype "input"))
      (node (ref "U$19") (pin "A1") (pinfunction "A1_A1") (pintype "passive"))
    )
    (net (code "3") (name "A1CFG") (class "Default")
      (node (ref "GND") (pin "A1") (pinfunction "A1_A1") (pintype "bidirectional"))
      (node (ref "R21") (pin "2") (pinfunction "2_2") (pintype "passive"))
      (node (ref "S1") (pin "1") (pinfunction "1_1") (pintype "passive"))
      (node (ref "S2") (pin "1") (pinfunction "1_1") (pintype "passive"))
    )
    (net (code "4") (name "A2") (class "Default")
      (node (ref "IC2") (pin "17") (pinfunction "A2_17") (pintype "input"))
      (node (ref "IC3") (pin "3") (pinfunction "A2_3") (pintype "input"))
      (node (ref "IC4") (pin "17") (pinfunction "A2_17") (pintype "input"))
      (node (ref "U$19") (pin "A2") (pinfunction "A2_A2") (pintype "passive"))
    )
    (net (code "5") (name "ADDR1") (class "Default")
      (node (ref "DIP3") (pin "P$1") (pinfunction "1_P$1") (pintype "passive"))
      (node (ref "GND") (pin "D6") (pinfunction "*D6_D6") (pintype "bidirectional"))
    )
    (net (code "6") (name "ADDR2") (class "Default")
      (node (ref "DIP3") (pin "P$4") (pinfunction "2_P$4") (pintype "passive"))
      (node (ref "GND") (pin "D7") (pinfunction "D7_D7") (pintype "bidirectional"))
    )
    (net (code "7") (name "ADDR3") (class "Default")
      (node (ref "DIP3") (pin "P$3") (pinfunction "4_P$3") (pintype "passive"))
      (node (ref "GND") (pin "D8") (pinfunction "D8_D8") (pintype "bidirectional"))
    )
    (net (code "8") (name "ADDR4") (class "Default")
      (node (ref "DIP3") (pin "P$6") (pinfunction "8_P$6") (pintype "passive"))
      (node (ref "GND") (pin "D9") (pinfunction "*D9_D9") (pintype "bidirectional"))
    )
    (net (code "9") (name "D2") (class "Default")
      (node (ref "GND") (pin "D2") (pinfunction "D2_D2") (pintype "bidirectional"))
      (node (ref "R3") (pin "2") (pinfunction "2_2") (pintype "passive"))
    )
    (net (code "10") (name "D3") (class "Default")
      (node (ref "GND") (pin "D3") (pinfunction "*D3_D3") (pintype "bidirectional"))
      (node (ref "R4") (pin "2") (pinfunction "2_2") (pintype "passive"))
    )
    (net (code "11") (name "FOLLOW_IRIS") (class "Default")
      (node (ref "C14") (pin "1") (pinfunction "1_1") (pintype "passive"))
      (node (ref "GND") (pin "A2") (pinfunction "A2_A2") (pintype "bidirectional"))
      (node (ref "R6") (pin "1") (pinfunction "1_1") (pintype "passive"))
      (node (ref "R7") (pin "2") (pinfunction "2_2") (pintype "passive"))
    )
    (net (code "12") (name "GND") (class "Default")
      (node (ref "B1") (pin "1") (pinfunction "SW1_1") (pintype "bidirectional"))
      (node (ref "B10") (pin "1") (pinfunction "SW1_1") (pintype "bidirectional"))
      (node (ref "B11") (pin "1") (pinfunction "SW1_1") (pintype "bidirectional"))
      (node (ref "B12") (pin "1") (pinfunction "SW1_1") (pintype "bidirectional"))
      (node (ref "B13") (pin "1") (pinfunction "SW1_1") (pintype "bidirectional"))
      (node (ref "B14") (pin "1") (pinfunction "SW1_1") (pintype "bidirectional"))
      (node (ref "B15") (pin "1") (pinfunction "SW1_1") (pintype "bidirectional"))
      (node (ref "B16") (pin "1") (pinfunction "SW1_1") (pintype "bidirectional"))
      (node (ref "B2") (pin "1") (pinfunction "SW1_1") (pintype "bidirectional"))
      (node (ref "B3") (pin "1") (pinfunction "SW1_1") (pintype "bidirectional"))
      (node (ref "B4") (pin "1") (pinfunction "SW1_1") (pintype "bidirectional"))
      (node (ref "B5") (pin "1") (pinfunction "SW1_1") (pintype "bidirectional"))
      (node (ref "B6") (pin "1") (pinfunction "SW1_1") (pintype "bidirectional"))
      (node (ref "B7") (pin "1") (pinfunction "SW1_1") (pintype "bidirectional"))
      (node (ref "B8") (pin "1") (pinfunction "SW1_1") (pintype "bidirectional"))
      (node (ref "B9") (pin "1") (pinfunction "SW1_1") (pintype "bidirectional"))
      (node (ref "C1") (pin "1") (pinfunction "1_1") (pintype "passive"))
      (node (ref "C10") (pin "2") (pinfunction "2_2") (pintype "passive"))
      (node (ref "C11") (pin "2") (pinfunction "2_2") (pintype "passive"))
      (node (ref "C12") (pin "2") (pinfunction "2_2") (pintype "passive"))
      (node (ref "C13") (pin "2") (pinfunction "2_2") (pintype "passive"))
      (node (ref "C14") (pin "2") (pinfunction "2_2") (pintype "passive"))
      (node (ref "C15") (pin "2") (pinfunction "2_2") (pintype "passive"))
      (node (ref "C16") (pin "2") (pinfunction "2_2") (pintype "passive"))
      (node (ref "C17") (pin "2") (pinfunction "2_2") (pintype "passive"))
      (node (ref "C18") (pin "2") (pinfunction "2_2") (pintype "passive"))
      (node (ref "C2") (pin "1") (pinfunction "1_1") (pintype "passive"))
      (node (ref "C3") (pin "2") (pinfunction "2_2") (pintype "passive"))
      (node (ref "C4") (pin "1") (pinfunction "1_1") (pintype "passive"))
      (node (ref "C5") (pin "2") (pinfunction "2_2") (pintype "passive"))
      (node (ref "C6") (pin "2") (pinfunction "2_2") (pintype "passive"))
      (node (ref "C7") (pin "2") (pinfunction "2_2") (pintype "passive"))
      (node (ref "C8") (pin "2") (pinfunction "2_2") (pintype "passive"))
      (node (ref "C9") (pin "2") (pinfunction "2_2") (pintype "passive"))
      (node (ref "DIP3") (pin "P$2") (pinfunction "GND_P$2") (pintype "passive"))
      (node (ref "DIP3") (pin "P$5") (pinfunction "GND_P$5") (pintype "passive"))
      (node (ref "GND") (pin "GND@0") (pinfunction "GND_GND@0") (pintype "bidirectional"))
      (node (ref "GND") (pin "GND@1") (pinfunction "GND_GND@1") (pintype "bidirectional"))
      (node (ref "GND") (pin "GND@2") (pinfunction "GND_GND@2") (pintype "bidirectional"))
      (node (ref "IC1") (pin "9") (pinfunction "GND_9") (pintype "power_in"))
      (node (ref "IC2") (pin "10") (pinfunction "VSS_10") (pintype "power_in"))
      (node (ref "IC2") (pin "15") (pinfunction "A0_15") (pintype "input"))
      (node (ref "IC3") (pin "14") (pinfunction "GND_14") (pintype "power_in"))
      (node (ref "IC3") (pin "23") (pinfunction "OE_23") (pintype "input"))
      (node (ref "IC3") (pin "25") (pinfunction "EXTCLK_25") (pintype "input"))
      (node (ref "IC4") (pin "10") (pinfunction "VSS_10") (pintype "power_in"))
      (node (ref "IC5") (pin "4") (pinfunction "V-_4") (pintype "power_in"))
      (node (ref "IC5") (pin "6") (pinfunction "-IN_6") (pintype "input"))
      (node (ref "JP2") (pin "3") (pinfunction "3_3") (pintype "passive"))
      (node (ref "JP3") (pin "1") (pinfunction "1_1") (pintype "passive"))
      (node (ref "JP5") (pin "1") (pinfunction "1_1") (pintype "passive"))
      (node (ref "K1") (pin "P1") (pinfunction "P_P1") (pintype "passive"))
      (node (ref "K1") (pin "P2") (pinfunction "P_P2") (pintype "passive"))
      (node (ref "K2") (pin "P1") (pinfunction "P_P1") (pintype "passive"))
      (node (ref "K2") (pin "P2") (pinfunction "P_P2") (pintype "passive"))
      (node (ref "OK1") (pin "5") (pinfunction "EMIT_5") (pintype "passive"))
      (node (ref "OK1") (pin "7") (pinfunction "EMIT_7") (pintype "passive"))
      (node (ref "PC1") (pin "-") (pinfunction "-_-") (pintype "passive"))
      (node (ref "PC2") (pin "-") (pinfunction "-_-") (pintype "passive"))
      (node (ref "R10") (pin "2") (pinfunction "2_2") (pintype "passive"))
      (node (ref "R21") (pin "1") (pinfunction "1_1") (pintype "passive"))
      (node (ref "R7") (pin "1") (pinfunction "1_1") (pintype "passive"))
      (node (ref "RESET") (pin "3") (pinfunction "3_3") (pintype "passive"))
      (node (ref "RESETA") (pin "3") (pinfunction "3_3") (pintype "passive"))
      (node (ref "S3") (pin "P$2") (pinfunction "P_P$2") (pintype "passive"))
      (node (ref "T6") (pin "2") (pinfunction "E_2") (pintype "passive"))
      (node (ref "U$19") (pin "L2") (pinfunction "GND_L2") (pintype "passive"))
      (node (ref "U$19") (pin "L3") (pinfunction "GND_L3") (pintype "passive"))
      (node (ref "U$20") (pin "P$1") (pinfunction "1_P$1") (pintype "passive"))
      (node (ref "U$4") (pin "P$1") (pinfunction "1_P$1") (pintype "passive"))
      (node (ref "U$7") (pin "K1") (pinfunction "P$1_K1") (pintype "bidirectional"))
      (node (ref "X6") (pin "1") (pinfunction "1_1") (pintype "passive"))
    )
    (net (code "13") (name "GPA0") (class "Default")
      (node (ref "B1") (pin "2") (pinfunction "SW2_2") (pintype "bidirectional"))
      (node (ref "IC4") (pin "21") (pinfunction "GPA0_21") (pintype "bidirectional"))
    )
    (net (code "14") (name "GPA1") (class "Default")
      (node (ref "B2") (pin "2") (pinfunction "SW2_2") (pintype "bidirectional"))
      (node (ref "IC4") (pin "22") (pinfunction "GPA1_22") (pintype "bidirectional"))
    )
    (net (code "15") (name "GPA2") (class "Default")
      (node (ref "B3") (pin "2") (pinfunction "SW2_2") (pintype "bidirectional"))
      (node (ref "IC4") (pin "23") (pinfunction "GPA2_23") (pintype "bidirectional"))
    )
    (net (code "16") (name "GPA3") (class "Default")
      (node (ref "B4") (pin "2") (pinfunction "SW2_2") (pintype "bidirectional"))
      (node (ref "IC4") (pin "24") (pinfunction "GPA3_24") (pintype "bidirectional"))
    )
    (net (code "17") (name "GPA4") (class "Default")
      (node (ref "B5") (pin "2") (pinfunction "SW2_2") (pintype "bidirectional"))
      (node (ref "IC4") (pin "25") (pinfunction "GPA4_25") (pintype "bidirectional"))
    )
    (net (code "18") (name "GPA5") (class "Default")
      (node (ref "B6") (pin "2") (pinfunction "SW2_2") (pintype "bidirectional"))
      (node (ref "IC4") (pin "26") (pinfunction "GPA5_26") (pintype "bidirectional"))
    )
    (net (code "19") (name "GPA6") (class "Default")
      (node (ref "B7") (pin "2") (pinfunction "SW2_2") (pintype "bidirectional"))
      (node (ref "IC4") (pin "27") (pinfunction "GPA6_27") (pintype "bidirectional"))
    )
    (net (code "20") (name "GPA7") (class "Default")
      (node (ref "B8") (pin "2") (pinfunction "SW2_2") (pintype "bidirectional"))
      (node (ref "IC4") (pin "28") (pinfunction "GPA7_28") (pintype "bidirectional"))
    )
    (net (code "21") (name "GPB0") (class "Default")
      (node (ref "B9") (pin "2") (pinfunction "SW2_2") (pintype "bidirectional"))
      (node (ref "IC4") (pin "1") (pinfunction "GPB0_1") (pintype "bidirectional"))
    )
    (net (code "22") (name "GPB1") (class "Default")
      (node (ref "B10") (pin "2") (pinfunction "SW2_2") (pintype "bidirectional"))
      (node (ref "IC4") (pin "2") (pinfunction "GPB1_2") (pintype "bidirectional"))
    )
    (net (code "23") (name "GPB2") (class "Default")
      (node (ref "B11") (pin "2") (pinfunction "SW2_2") (pintype "bidirectional"))
      (node (ref "IC4") (pin "3") (pinfunction "GPB2_3") (pintype "bidirectional"))
    )
    (net (code "24") (name "GPB3") (class "Default")
      (node (ref "B12") (pin "2") (pinfunction "SW2_2") (pintype "bidirectional"))
      (node (ref "IC4") (pin "4") (pinfunction "GPB3_4") (pintype "bidirectional"))
    )
    (net (code "25") (name "GPB4") (class "Default")
      (node (ref "B13") (pin "2") (pinfunction "SW2_2") (pintype "bidirectional"))
      (node (ref "IC4") (pin "5") (pinfunction "GPB4_5") (pintype "bidirectional"))
    )
    (net (code "26") (name "GPB5") (class "Default")
      (node (ref "B14") (pin "2") (pinfunction "SW2_2") (pintype "bidirectional"))
      (node (ref "IC4") (pin "6") (pinfunction "GPB5_6") (pintype "bidirectional"))
    )
    (net (code "27") (name "GPB6") (class "Default")
      (node (ref "B15") (pin "2") (pinfunction "SW2_2") (pintype "bidirectional"))
      (node (ref "IC4") (pin "7") (pinfunction "GPB6_7") (pintype "bidirectional"))
    )
    (net (code "28") (name "GPB7") (class "Default")
      (node (ref "B16") (pin "2") (pinfunction "SW2_2") (pintype "bidirectional"))
      (node (ref "IC4") (pin "8") (pinfunction "GPB7_8") (pintype "bidirectional"))
    )
    (net (code "29") (name "I2C_SCL") (class "Default")
      (node (ref "IC2") (pin "12") (pinfunction "SCL_12") (pintype "input"))
      (node (ref "IC3") (pin "26") (pinfunction "SCL_26") (pintype "input"))
      (node (ref "IC4") (pin "12") (pinfunction "SCL_12") (pintype "input"))
      (node (ref "JP4") (pin "2") (pinfunction "2_2") (pintype "passive"))
      (node (ref "R2") (pin "1") (pinfunction "1_1") (pintype "passive"))
    )
    (net (code "30") (name "I2C_SDA") (class "Default")
      (node (ref "IC2") (pin "13") (pinfunction "SDA_13") (pintype "bidirectional"))
      (node (ref "IC3") (pin "27") (pinfunction "SDA_27") (pintype "input"))
      (node (ref "IC4") (pin "13") (pinfunction "SDA_13") (pintype "bidirectional"))
      (node (ref "JP4") (pin "1") (pinfunction "1_1") (pintype "passive"))
      (node (ref "R1") (pin "1") (pinfunction "1_1") (pintype "passive"))
    )
    (net (code "31") (name "IRIS_CONTROL") (class "Default")
      (node (ref "C18") (pin "1") (pinfunction "1_1") (pintype "passive"))
      (node (ref "IC5") (pin "1") (pinfunction "OUT_1") (pintype "output"))
      (node (ref "JP2") (pin "5") (pinfunction "5_5") (pintype "passive"))
      (node (ref "R9") (pin "1") (pinfunction "1_1") (pintype "passive"))
    )
    (net (code "32") (name "L0") (class "Default")
      (node (ref "B1") (pin "L1") (pinfunction "L1_L1") (pintype "bidirectional"))
      (node (ref "B1") (pin "L2") (pinfunction "L2_L2") (pintype "bidirectional"))
      (node (ref "R37") (pin "1") (pinfunction "1_1") (pintype "passive"))
    )
    (net (code "33") (name "L1") (class "Default")
      (node (ref "B2") (pin "L1") (pinfunction "L1_L1") (pintype "bidirectional"))
      (node (ref "B2") (pin "L2") (pinfunction "L2_L2") (pintype "bidirectional"))
      (node (ref "R36") (pin "1") (pinfunction "1_1") (pintype "passive"))
    )
    (net (code "34") (name "L2") (class "Default")
      (node (ref "B3") (pin "L1") (pinfunction "L1_L1") (pintype "bidirectional"))
      (node (ref "B3") (pin "L2") (pinfunction "L2_L2") (pintype "bidirectional"))
      (node (ref "R35") (pin "1") (pinfunction "1_1") (pintype "passive"))
    )
    (net (code "35") (name "L3") (class "Default")
      (node (ref "B4") (pin "L1") (pinfunction "L1_L1") (pintype "bidirectional"))
      (node (ref "B4") (pin "L2") (pinfunction "L2_L2") (pintype "bidirectional"))
      (node (ref "R34") (pin "1") (pinfunction "1_1") (pintype "passive"))
    )
    (net (code "36") (name "L4") (class "Default")
      (node (ref "B5") (pin "L1") (pinfunction "L1_L1") (pintype "bidirectional"))
      (node (ref "B5") (pin "L2") (pinfunction "L2_L2") (pintype "bidirectional"))
      (node (ref "R33") (pin "1") (pinfunction "1_1") (pintype "passive"))
    )
    (net (code "37") (name "L5") (class "Default")
      (node (ref "B6") (pin "L1") (pinfunction "L1_L1") (pintype "bidirectional"))
      (node (ref "B6") (pin "L2") (pinfunction "L2_L2") (pintype "bidirectional"))
      (node (ref "R32") (pin "1") (pinfunction "1_1") (pintype "passive"))
    )
    (net (code "38") (name "L6") (class "Default")
      (node (ref "B7") (pin "L1") (pinfunction "L1_L1") (pintype "bidirectional"))
      (node (ref "B7") (pin "L2") (pinfunction "L2_L2") (pintype "bidirectional"))
      (node (ref "R31") (pin "1") (pinfunction "1_1") (pintype "passive"))
    )
    (net (code "39") (name "L7") (class "Default")
      (node (ref "B8") (pin "L1") (pinfunction "L1_L1") (pintype "bidirectional"))
      (node (ref "B8") (pin "L2") (pinfunction "L2_L2") (pintype "bidirectional"))
      (node (ref "R30") (pin "1") (pinfunction "1_1") (pintype "passive"))
    )
    (net (code "40") (name "L8") (class "Default")
      (node (ref "B9") (pin "L1") (pinfunction "L1_L1") (pintype "bidirectional"))
      (node (ref "B9") (pin "L2") (pinfunction "L2_L2") (pintype "bidirectional"))
      (node (ref "R29") (pin "1") (pinfunction "1_1") (pintype "passive"))
    )
    (net (code "41") (name "L9") (class "Default")
      (node (ref "B10") (pin "L1") (pinfunction "L1_L1") (pintype "bidirectional"))
      (node (ref "B10") (pin "L2") (pinfunction "L2_L2") (pintype "bidirectional"))
      (node (ref "R28") (pin "1") (pinfunction "1_1") (pintype "passive"))
    )
    (net (code "42") (name "L10") (class "Default")
      (node (ref "B11") (pin "L1") (pinfunction "L1_L1") (pintype "bidirectional"))
      (node (ref "B11") (pin "L2") (pinfunction "L2_L2") (pintype "bidirectional"))
      (node (ref "R27") (pin "1") (pinfunction "1_1") (pintype "passive"))
    )
    (net (code "43") (name "L11") (class "Default")
      (node (ref "B12") (pin "L1") (pinfunction "L1_L1") (pintype "bidirectional"))
      (node (ref "B12") (pin "L2") (pinfunction "L2_L2") (pintype "bidirectional"))
      (node (ref "R26") (pin "1") (pinfunction "1_1") (pintype "passive"))
    )
    (net (code "44") (name "L12") (class "Default")
      (node (ref "B13") (pin "L1") (pinfunction "L1_L1") (pintype "bidirectional"))
      (node (ref "B13") (pin "L2") (pinfunction "L2_L2") (pintype "bidirectional"))
      (node (ref "R25") (pin "1") (pinfunction "1_1") (pintype "passive"))
    )
    (net (code "45") (name "L13") (class "Default")
      (node (ref "B14") (pin "L1") (pinfunction "L1_L1") (pintype "bidirectional"))
      (node (ref "B14") (pin "L2") (pinfunction "L2_L2") (pintype "bidirectional"))
      (node (ref "R24") (pin "1") (pinfunction "1_1") (pintype "passive"))
    )
    (net (code "46") (name "L14") (class "Default")
      (node (ref "B15") (pin "L1") (pinfunction "L1_L1") (pintype "bidirectional"))
      (node (ref "B15") (pin "L2") (pinfunction "L2_L2") (pintype "bidirectional"))
      (node (ref "R23") (pin "1") (pinfunction "1_1") (pintype "passive"))
    )
    (net (code "47") (name "L15") (class "Default")
      (node (ref "B16") (pin "L1") (pinfunction "L1_L1") (pintype "bidirectional"))
      (node (ref "B16") (pin "L2") (pinfunction "L2_L2") (pintype "bidirectional"))
      (node (ref "R22") (pin "1") (pinfunction "1_1") (pintype "passive"))
    )
    (net (code "48") (name "Net-(C17-Pad1)") (class "Default")
      (node (ref "C17") (pin "1") (pinfunction "1_1") (pintype "passive"))
      (node (ref "R11") (pin "1") (pinfunction "1_1") (pintype "passive"))
      (node (ref "R12") (pin "2") (pinfunction "2_2") (pintype "passive"))
    )
    (net (code "49") (name "Net-(D7-A)") (class "Default")
      (node (ref "D7") (pin "2") (pinfunction "A_2") (pintype "passive"))
      (node (ref "IO2") (pin "1") (pinfunction "1_1") (pintype "passive"))
      (node (ref "OK1") (pin "4") (pinfunction "C_4") (pintype "passive"))
    )
    (net (code "50") (name "Net-(D7-C)") (class "Default")
      (node (ref "D7") (pin "1") (pinfunction "C_1") (pintype "passive"))
      (node (ref "OK1") (pin "3") (pinfunction "A_3") (pintype "passive"))
      (node (ref "R13") (pin "2") (pinfunction "2_2") (pintype "passive"))
    )
    (net (code "51") (name "Net-(D8-A)") (class "Default")
      (node (ref "D8") (pin "2") (pinfunction "A_2") (pintype "passive"))
      (node (ref "IO1") (pin "1") (pinfunction "1_1") (pintype "passive"))
      (node (ref "OK1") (pin "2") (pinfunction "C_2") (pintype "passive"))
    )
    (net (code "52") (name "Net-(D8-C)") (class "Default")
      (node (ref "D8") (pin "1") (pinfunction "C_1") (pintype "passive"))
      (node (ref "OK1") (pin "1") (pinfunction "A_1") (pintype "passive"))
      (node (ref "R14") (pin "2") (pinfunction "2_2") (pintype "passive"))
    )
    (net (code "53") (name "Net-(GND-Pad5V)") (class "Default")
      (node (ref "GND") (pin "5V") (pinfunction "5V_5V") (pintype "bidirectional"))
      (node (ref "L4") (pin "1") (pinfunction "1_1") (pintype "passive"))
      (node (ref "PC2") (pin "+") (pinfunction "+_+") (pintype "passive"))
    )
    (net (code "54") (name "Net-(IC1-I1)") (class "Default")
      (node (ref "IC1") (pin "1") (pinfunction "I1_1") (pintype "input"))
      (node (ref "IC2") (pin "1") (pinfunction "GPB0_1") (pintype "bidirectional"))
    )
    (net (code "55") (name "Net-(IC1-I2)") (class "Default")
      (node (ref "IC1") (pin "2") (pinfunction "I2_2") (pintype "input"))
      (node (ref "IC2") (pin "2") (pinfunction "GPB1_2") (pintype "bidirectional"))
    )
    (net (code "56") (name "Net-(IC1-I3)") (class "Default")
      (node (ref "IC1") (pin "3") (pinfunction "I3_3") (pintype "input"))
      (node (ref "IC2") (pin "3") (pinfunction "GPB2_3") (pintype "bidirectional"))
    )
    (net (code "57") (name "Net-(IC1-I4)") (class "Default")
      (node (ref "IC1") (pin "4") (pinfunction "I4_4") (pintype "input"))
      (node (ref "IC2") (pin "4") (pinfunction "GPB3_4") (pintype "bidirectional"))
    )
    (net (code "58") (name "Net-(IC1-I5)") (class "Default")
      (node (ref "IC1") (pin "5") (pinfunction "I5_5") (pintype "input"))
      (node (ref "IC2") (pin "5") (pinfunction "GPB4_5") (pintype "bidirectional"))
    )
    (net (code "59") (name "Net-(IC1-I6)") (class "Default")
      (node (ref "IC1") (pin "6") (pinfunction "I6_6") (pintype "input"))
      (node (ref "IC2") (pin "6") (pinfunction "GPB5_6") (pintype "bidirectional"))
    )
    (net (code "60") (name "Net-(IC1-I7)") (class "Default")
      (node (ref "IC1") (pin "7") (pinfunction "I7_7") (pintype "input"))
      (node (ref "IC2") (pin "7") (pinfunction "GPB6_7") (pintype "bidirectional"))
    )
    (net (code "61") (name "Net-(IC1-I8)") (class "Default")
      (node (ref "IC1") (pin "8") (pinfunction "I8_8") (pintype "input"))
      (node (ref "IC2") (pin "8") (pinfunction "GPB7_8") (pintype "bidirectional"))
    )
    (net (code "62") (name "Net-(IC1-O1)") (class "Default")
      (node (ref "IC1") (pin "18") (pinfunction "O1_18") (pintype "open_collector"))
      (node (ref "K1") (pin "16") (pinfunction "2_16") (pintype "passive"))
    )
    (net (code "63") (name "Net-(IC1-O2)") (class "Default")
      (node (ref "IC1") (pin "17") (pinfunction "O2_17") (pintype "open_collector"))
      (node (ref "K2") (pin "16") (pinfunction "2_16") (pintype "passive"))
    )
    (net (code "64") (name "Net-(IC2-GPA0)") (class "Default")
      (node (ref "IC2") (pin "21") (pinfunction "GPA0_21") (pintype "bidirectional"))
      (node (ref "OK1") (pin "8") (pinfunction "COL_8") (pintype "passive"))
    )
    (net (code "65") (name "Net-(IC2-GPA1)") (class "Default")
      (node (ref "IC2") (pin "22") (pinfunction "GPA1_22") (pintype "bidirectional"))
      (node (ref "OK1") (pin "6") (pinfunction "COL_6") (pintype "passive"))
    )
    (net (code "66") (name "Net-(IC3-L0)") (class "Default")
      (node (ref "IC3") (pin "6") (pinfunction "L0_6") (pintype "output"))
      (node (ref "R37") (pin "2") (pinfunction "2_2") (pintype "passive"))
    )
    (net (code "67") (name "Net-(IC3-L1)") (class "Default")
      (node (ref "IC3") (pin "7") (pinfunction "L1_7") (pintype "output"))
      (node (ref "R36") (pin "2") (pinfunction "2_2") (pintype "passive"))
    )
    (net (code "68") (name "Net-(IC3-L2)") (class "Default")
      (node (ref "IC3") (pin "8") (pinfunction "L2_8") (pintype "output"))
      (node (ref "R35") (pin "2") (pinfunction "2_2") (pintype "passive"))
    )
    (net (code "69") (name "Net-(IC3-L3)") (class "Default")
      (node (ref "IC3") (pin "9") (pinfunction "L3_9") (pintype "output"))
      (node (ref "R34") (pin "2") (pinfunction "2_2") (pintype "passive"))
    )
    (net (code "70") (name "Net-(IC3-L4)") (class "Default")
      (node (ref "IC3") (pin "10") (pinfunction "L4_10") (pintype "output"))
      (node (ref "R33") (pin "2") (pinfunction "2_2") (pintype "passive"))
    )
    (net (code "71") (name "Net-(IC3-L5)") (class "Default")
      (node (ref "IC3") (pin "11") (pinfunction "L5_11") (pintype "output"))
      (node (ref "R32") (pin "2") (pinfunction "2_2") (pintype "passive"))
    )
    (net (code "72") (name "Net-(IC3-L6)") (class "Default")
      (node (ref "IC3") (pin "12") (pinfunction "L6_12") (pintype "output"))
      (node (ref "R31") (pin "2") (pinfunction "2_2") (pintype "passive"))
    )
    (net (code "73") (name "Net-(IC3-L7)") (class "Default")
      (node (ref "IC3") (pin "13") (pinfunction "L7_13") (pintype "output"))
      (node (ref "R30") (pin "2") (pinfunction "2_2") (pintype "passive"))
    )
    (net (code "74") (name "Net-(IC3-L8)") (class "Default")
      (node (ref "IC3") (pin "15") (pinfunction "L8_15") (pintype "output"))
      (node (ref "R29") (pin "2") (pinfunction "2_2") (pintype "passive"))
    )
    (net (code "75") (name "Net-(IC3-L9)") (class "Default")
      (node (ref "IC3") (pin "16") (pinfunction "L9_16") (pintype "output"))
      (node (ref "R28") (pin "2") (pinfunction "2_2") (pintype "passive"))
    )
    (net (code "76") (name "Net-(IC3-L10)") (class "Default")
      (node (ref "IC3") (pin "17") (pinfunction "L10_17") (pintype "output"))
      (node (ref "R27") (pin "2") (pinfunction "2_2") (pintype "passive"))
    )
    (net (code "77") (name "Net-(IC3-L11)") (class "Default")
      (node (ref "IC3") (pin "18") (pinfunction "L11_18") (pintype "output"))
      (node (ref "R26") (pin "2") (pinfunction "2_2") (pintype "passive"))
    )
    (net (code "78") (name "Net-(IC3-L12)") (class "Default")
      (node (ref "IC3") (pin "19") (pinfunction "L12_19") (pintype "output"))
      (node (ref "R25") (pin "2") (pinfunction "2_2") (pintype "passive"))
    )
    (net (code "79") (name "Net-(IC3-L13)") (class "Default")
      (node (ref "IC3") (pin "20") (pinfunction "L13_20") (pintype "output"))
      (node (ref "R24") (pin "2") (pinfunction "2_2") (pintype "passive"))
    )
    (net (code "80") (name "Net-(IC3-L14)") (class "Default")
      (node (ref "IC3") (pin "21") (pinfunction "L14_21") (pintype "output"))
      (node (ref "R23") (pin "2") (pinfunction "2_2") (pintype "passive"))
    )
    (net (code "81") (name "Net-(IC3-L15)") (class "Default")
      (node (ref "IC3") (pin "22") (pinfunction "L15_22") (pintype "output"))
      (node (ref "R22") (pin "2") (pinfunction "2_2") (pintype "passive"))
    )
    (net (code "82") (name "Net-(IC5A-+IN)") (class "Default")
      (node (ref "C16") (pin "1") (pinfunction "1_1") (pintype "passive"))
      (node (ref "IC5") (pin "3") (pinfunction "+IN_3") (pintype "input"))
      (node (ref "R12") (pin "1") (pinfunction "1_1") (pintype "passive"))
    )
    (net (code "83") (name "Net-(IC5A--IN)") (class "Default")
      (node (ref "IC5") (pin "2") (pinfunction "-IN_2") (pintype "input"))
      (node (ref "R10") (pin "1") (pinfunction "1_1") (pintype "passive"))
      (node (ref "R9") (pin "2") (pinfunction "2_2") (pintype "passive"))
    )
    (net (code "84") (name "Net-(JP2-Pad7)") (class "Default")
      (node (ref "JP2") (pin "7") (pinfunction "7_7") (pintype "passive"))
      (node (ref "R6") (pin "2") (pinfunction "2_2") (pintype "passive"))
    )
    (net (code "85") (name "Net-(JP3-Pad4)") (class "Default")
      (node (ref "JP3") (pin "4") (pinfunction "4_4") (pintype "passive"))
      (node (ref "JP5") (pin "4") (pinfunction "4_4") (pintype "passive"))
    )
    (net (code "86") (name "Net-(JP3-Pad5)") (class "Default")
      (node (ref "JP3") (pin "5") (pinfunction "5_5") (pintype "passive"))
      (node (ref "JP5") (pin "5") (pinfunction "5_5") (pintype "passive"))
    )
    (net (code "87") (name "Net-(JP3-Pad6)") (class "Default")
      (node (ref "JP3") (pin "6") (pinfunction "6_6") (pintype "passive"))
      (node (ref "JP5") (pin "6") (pinfunction "6_6") (pintype "passive"))
    )
    (net (code "88") (name "Net-(K1B-S)") (class "Default")
      (node (ref "IO1") (pin "3") (pinfunction "3_3") (pintype "passive"))
      (node (ref "K1") (pin "S1") (pinfunction "S_S1") (pintype "passive"))
    )
    (net (code "89") (name "Net-(K2B-S)") (class "Default")
      (node (ref "IO2") (pin "3") (pinfunction "3_3") (pintype "passive"))
      (node (ref "K2") (pin "S1") (pinfunction "S_S1") (pintype "passive"))
    )
    (net (code "90") (name "Net-(S3-O)") (class "Default")
      (node (ref "R8") (pin "1") (pinfunction "1_1") (pintype "passive"))
      (node (ref "S3") (pin "P$1") (pinfunction "O_P$1") (pintype "passive"))
    )
    (net (code "91") (name "Net-(S3-S)") (class "Default")
      (node (ref "JP2") (pin "4") (pinfunction "4_4") (pintype "passive"))
      (node (ref "R5") (pin "1") (pinfunction "1_1") (pintype "passive"))
      (node (ref "S3") (pin "P$3") (pinfunction "S_P$3") (pintype "passive"))
    )
    (net (code "92") (name "Net-(T6-B)") (class "Default")
      (node (ref "R39") (pin "1") (pinfunction "1_1") (pintype "passive"))
      (node (ref "T6") (pin "1") (pinfunction "B_1") (pintype "passive"))
    )
    (net (code "93") (name "Net-(T6-C)") (class "Default")
      (node (ref "T6") (pin "3") (pinfunction "C_3") (pintype "passive"))
      (node (ref "X6") (pin "3") (pinfunction "1_3") (pintype "passive"))
    )
    (net (code "94") (name "Net-(U$7-P$2)") (class "Default")
      (node (ref "R4") (pin "1") (pinfunction "1_1") (pintype "passive"))
      (node (ref "U$7") (pin "A2") (pinfunction "P$2_A2") (pintype "bidirectional"))
    )
    (net (code "95") (name "Net-(U$7-P$3)") (class "Default")
      (node (ref "R3") (pin "1") (pinfunction "1_1") (pintype "passive"))
      (node (ref "U$7") (pin "A3") (pinfunction "P$3_A3") (pintype "bidirectional"))
    )
    (net (code "96") (name "Net-(U$12-C)") (class "Default")
      (node (ref "R8") (pin "2") (pinfunction "2_2") (pintype "passive"))
      (node (ref "U$12") (pin "K") (pinfunction "C_K") (pintype "passive"))
    )
    (net (code "97") (name "Net-(X6B-1)") (class "Default")
      (node (ref "C3") (pin "1") (pinfunction "1_1") (pintype "passive"))
      (node (ref "JP2") (pin "6") (pinfunction "6_6") (pintype "passive"))
      (node (ref "L1") (pin "1") (pinfunction "1_1") (pintype "passive"))
      (node (ref "PC1") (pin "+") (pinfunction "+_+") (pintype "passive"))
      (node (ref "X6") (pin "2") (pinfunction "1_2") (pintype "passive"))
    )
    (net (code "98") (name "Net-(X6D-1)") (class "Default")
      (node (ref "IO1") (pin "2") (pinfunction "2_2") (pintype "passive"))
      (node (ref "X6") (pin "4") (pinfunction "1_4") (pintype "passive"))
    )
    (net (code "99") (name "Net-(X6E-1)") (class "Default")
      (node (ref "IO2") (pin "2") (pinfunction "2_2") (pintype "passive"))
      (node (ref "X6") (pin "5") (pinfunction "1_5") (pintype "passive"))
    )
    (net (code "100") (name "PRV_TALLY") (class "Default")
      (node (ref "GND") (pin "D4") (pinfunction "D4_D4") (pintype "bidirectional"))
      (node (ref "R39") (pin "2") (pinfunction "2_2") (pintype "passive"))
    )
    (net (code "101") (name "PWM_IRIS") (class "Default")
      (node (ref "GND") (pin "D5") (pinfunction "*D5_D5") (pintype "bidirectional"))
      (node (ref "R11") (pin "2") (pinfunction "2_2") (pintype "passive"))
    )
    (net (code "102") (name "RES") (class "Default")
      (node (ref "GND") (pin "RES") (pinfunction "RES_RES") (pintype "bidirectional"))
      (node (ref "RESET") (pin "1") (pinfunction "1_1") (pintype "passive"))
      (node (ref "RESETA") (pin "1") (pinfunction "1_1") (pintype "passive"))
    )
    (net (code "103") (name "VIN") (class "Default")
      (node (ref "C15") (pin "1") (pinfunction "1_1") (pintype "passive"))
      (node (ref "C7") (pin "1") (pinfunction "1_1") (pintype "passive"))
      (node (ref "C9") (pin "1") (pinfunction "1_1") (pintype "passive"))
      (node (ref "GND") (pin "VIN") (pinfunction "VIN_VIN") (pintype "bidirectional"))
      (node (ref "IC5") (pin "8") (pinfunction "V+_8") (pintype "power_in"))
      (node (ref "L1") (pin "2") (pinfunction "2_2") (pintype "passive"))
    )
    (net (code "104") (name "unconnected-(B1-PadL3)") (class "Default")
      (node (ref "B1") (pin "L3") (pinfunction "L3_L3") (pintype "bidirectional"))
    )
    (net (code "105") (name "unconnected-(B1-PadL4)") (class "Default")
      (node (ref "B1") (pin "L4") (pinfunction "L4_L4") (pintype "bidirectional"))
    )
    (net (code "106") (name "unconnected-(B1-PadLC2)") (class "Default")
      (node (ref "B1") (pin "LC2") (pinfunction "LC2_LC2") (pintype "bidirectional"))
    )
    (net (code "107") (name "unconnected-(B2-PadL3)") (class "Default")
      (node (ref "B2") (pin "L3") (pinfunction "L3_L3") (pintype "bidirectional"))
    )
    (net (code "108") (name "unconnected-(B2-PadL4)") (class "Default")
      (node (ref "B2") (pin "L4") (pinfunction "L4_L4") (pintype "bidirectional"))
    )
    (net (code "109") (name "unconnected-(B2-PadLC2)") (class "Default")
      (node (ref "B2") (pin "LC2") (pinfunction "LC2_LC2") (pintype "bidirectional"))
    )
    (net (code "110") (name "unconnected-(B3-PadL3)") (class "Default")
      (node (ref "B3") (pin "L3") (pinfunction "L3_L3") (pintype "bidirectional"))
    )
    (net (code "111") (name "unconnected-(B3-PadL4)") (class "Default")
      (node (ref "B3") (pin "L4") (pinfunction "L4_L4") (pintype "bidirectional"))
    )
    (net (code "112") (name "unconnected-(B3-PadLC2)") (class "Default")
      (node (ref "B3") (pin "LC2") (pinfunction "LC2_LC2") (pintype "bidirectional"))
    )
    (net (code "113") (name "unconnected-(B4-PadL3)") (class "Default")
      (node (ref "B4") (pin "L3") (pinfunction "L3_L3") (pintype "bidirectional"))
    )
    (net (code "114") (name "unconnected-(B4-PadL4)") (class "Default")
      (node (ref "B4") (pin "L4") (pinfunction "L4_L4") (pintype "bidirectional"))
    )
    (net (code "115") (name "unconnected-(B4-PadLC2)") (class "Default")
      (node (ref "B4") (pin "LC2") (pinfunction "LC2_LC2") (pintype "bidirectional"))
    )
    (net (code "116") (name "unconnected-(B5-PadL3)") (class "Default")
      (node (ref "B5") (pin "L3") (pinfunction "L3_L3") (pintype "bidirectional"))
    )
    (net (code "117") (name "unconnected-(B5-PadL4)") (class "Default")
      (node (ref "B5") (pin "L4") (pinfunction "L4_L4") (pintype "bidirectional"))
    )
    (net (code "118") (name "unconnected-(B5-PadLC2)") (class "Default")
      (node (ref "B5") (pin "LC2") (pinfunction "LC2_LC2") (pintype "bidirectional"))
    )
    (net (code "119") (name "unconnected-(B6-PadL3)") (class "Default")
      (node (ref "B6") (pin "L3") (pinfunction "L3_L3") (pintype "bidirectional"))
    )
    (net (code "120") (name "unconnected-(B6-PadL4)") (class "Default")
      (node (ref "B6") (pin "L4") (pinfunction "L4_L4") (pintype "bidirectional"))
    )
    (net (code "121") (name "unconnected-(B6-PadLC2)") (class "Default")
      (node (ref "B6") (pin "LC2") (pinfunction "LC2_LC2") (pintype "bidirectional"))
    )
    (net (code "122") (name "unconnected-(B7-PadL3)") (class "Default")
      (node (ref "B7") (pin "L3") (pinfunction "L3_L3") (pintype "bidirectional"))
    )
    (net (code "123") (name "unconnected-(B7-PadL4)") (class "Default")
      (node (ref "B7") (pin "L4") (pinfunction "L4_L4") (pintype "bidirectional"))
    )
    (net (code "124") (name "unconnected-(B7-PadLC2)") (class "Default")
      (node (ref "B7") (pin "LC2") (pinfunction "LC2_LC2") (pintype "bidirectional"))
    )
    (net (code "125") (name "unconnected-(B8-PadL3)") (class "Default")
      (node (ref "B8") (pin "L3") (pinfunction "L3_L3") (pintype "bidirectional"))
    )
    (net (code "126") (name "unconnected-(B8-PadL4)") (class "Default")
      (node (ref "B8") (pin "L4") (pinfunction "L4_L4") (pintype "bidirectional"))
    )
    (net (code "127") (name "unconnected-(B8-PadLC2)") (class "Default")
      (node (ref "B8") (pin "LC2") (pinfunction "LC2_LC2") (pintype "bidirectional"))
    )
    (net (code "128") (name "unconnected-(B9-PadL3)") (class "Default")
      (node (ref "B9") (pin "L3") (pinfunction "L3_L3") (pintype "bidirectional"))
    )
    (net (code "129") (name "unconnected-(B9-PadL4)") (class "Default")
      (node (ref "B9") (pin "L4") (pinfunction "L4_L4") (pintype "bidirectional"))
    )
    (net (code "130") (name "unconnected-(B9-PadLC2)") (class "Default")
      (node (ref "B9") (pin "LC2") (pinfunction "LC2_LC2") (pintype "bidirectional"))
    )
    (net (code "131") (name "unconnected-(B10-PadL3)") (class "Default")
      (node (ref "B10") (pin "L3") (pinfunction "L3_L3") (pintype "bidirectional"))
    )
    (net (code "132") (name "unconnected-(B10-PadL4)") (class "Default")
      (node (ref "B10") (pin "L4") (pinfunction "L4_L4") (pintype "bidirectional"))
    )
    (net (code "133") (name "unconnected-(B10-PadLC2)") (class "Default")
      (node (ref "B10") (pin "LC2") (pinfunction "LC2_LC2") (pintype "bidirectional"))
    )
    (net (code "134") (name "unconnected-(B11-PadL3)") (class "Default")
      (node (ref "B11") (pin "L3") (pinfunction "L3_L3") (pintype "bidirectional"))
    )
    (net (code "135") (name "unconnected-(B11-PadL4)") (class "Default")
      (node (ref "B11") (pin "L4") (pinfunction "L4_L4") (pintype "bidirectional"))
    )
    (net (code "136") (name "unconnected-(B11-PadLC2)") (class "Default")
      (node (ref "B11") (pin "LC2") (pinfunction "LC2_LC2") (pintype "bidirectional"))
    )
    (net (code "137") (name "unconnected-(B12-PadL3)") (class "Default")
      (node (ref "B12") (pin "L3") (pinfunction "L3_L3") (pintype "bidirectional"))
    )
    (net (code "138") (name "unconnected-(B12-PadL4)") (class "Default")
      (node (ref "B12") (pin "L4") (pinfunction "L4_L4") (pintype "bidirectional"))
    )
    (net (code "139") (name "unconnected-(B12-PadLC2)") (class "Default")
      (node (ref "B12") (pin "LC2") (pinfunction "LC2_LC2") (pintype "bidirectional"))
    )
    (net (code "140") (name "unconnected-(B13-PadL3)") (class "Default")
      (node (ref "B13") (pin "L3") (pinfunction "L3_L3") (pintype "bidirectional"))
    )
    (net (code "141") (name "unconnected-(B13-PadL4)") (class "Default")
      (node (ref "B13") (pin "L4") (pinfunction "L4_L4") (pintype "bidirectional"))
    )
    (net (code "142") (name "unconnected-(B13-PadLC2)") (class "Default")
      (node (ref "B13") (pin "LC2") (pinfunction "LC2_LC2") (pintype "bidirectional"))
    )
    (net (code "143") (name "unconnected-(B14-PadL3)") (class "Default")
      (node (ref "B14") (pin "L3") (pinfunction "L3_L3") (pintype "bidirectional"))
    )
    (net (code "144") (name "unconnected-(B14-PadL4)") (class "Default")
      (node (ref "B14") (pin "L4") (pinfunction "L4_L4") (pintype "bidirectional"))
    )
    (net (code "145") (name "unconnected-(B14-PadLC2)") (class "Default")
      (node (ref "B14") (pin "LC2") (pinfunction "LC2_LC2") (pintype "bidirectional"))
    )
    (net (code "146") (name "unconnected-(B15-PadL3)") (class "Default")
      (node (ref "B15") (pin "L3") (pinfunction "L3_L3") (pintype "bidirectional"))
    )
    (net (code "147") (name "unconnected-(B15-PadL4)") (class "Default")
      (node (ref "B15") (pin "L4") (pinfunction "L4_L4") (pintype "bidirectional"))
    )
    (net (code "148") (name "unconnected-(B15-PadLC2)") (class "Default")
      (node (ref "B15") (pin "LC2") (pinfunction "LC2_LC2") (pintype "bidirectional"))
    )
    (net (code "149") (name "unconnected-(B16-PadL3)") (class "Default")
      (node (ref "B16") (pin "L3") (pinfunction "L3_L3") (pintype "bidirectional"))
    )
    (net (code "150") (name "unconnected-(B16-PadL4)") (class "Default")
      (node (ref "B16") (pin "L4") (pinfunction "L4_L4") (pintype "bidirectional"))
    )
    (net (code "151") (name "unconnected-(B16-PadLC2)") (class "Default")
      (node (ref "B16") (pin "LC2") (pinfunction "LC2_LC2") (pintype "bidirectional"))
    )
    (net (code "152") (name "unconnected-(D1-A-Pad2)") (class "Default")
      (node (ref "D1") (pin "2") (pinfunction "A_2") (pintype "passive"))
    )
    (net (code "153") (name "unconnected-(D1-C-Pad1)") (class "Default")
      (node (ref "D1") (pin "1") (pinfunction "C_1") (pintype "passive"))
    )
    (net (code "154") (name "unconnected-(D2-A-Pad2)") (class "Default")
      (node (ref "D2") (pin "2") (pinfunction "A_2") (pintype "passive"))
    )
    (net (code "155") (name "unconnected-(D2-C-Pad1)") (class "Default")
      (node (ref "D2") (pin "1") (pinfunction "C_1") (pintype "passive"))
    )
    (net (code "156") (name "unconnected-(GND-*D10-PadD10)") (class "Default")
      (node (ref "GND") (pin "D10") (pinfunction "*D10_D10") (pintype "bidirectional"))
    )
    (net (code "157") (name "unconnected-(GND-*D11-PadD11)") (class "Default")
      (node (ref "GND") (pin "D11") (pinfunction "*D11_D11") (pintype "bidirectional"))
    )
    (net (code "158") (name "unconnected-(GND-Pad3.3V)") (class "Default")
      (node (ref "GND") (pin "3.3V") (pinfunction "3.3V_3.3V") (pintype "bidirectional"))
    )
    (net (code "159") (name "unconnected-(GND-PadA0)") (class "Default")
      (node (ref "GND") (pin "A0") (pinfunction "A0_A0") (pintype "bidirectional"))
    )
    (net (code "160") (name "unconnected-(GND-PadA3)") (class "Default")
      (node (ref "GND") (pin "A3") (pinfunction "A3_A3") (pintype "bidirectional"))
    )
    (net (code "161") (name "unconnected-(GND-PadA4)") (class "Default")
      (node (ref "GND") (pin "A4") (pinfunction "A4_A4") (pintype "bidirectional"))
    )
    (net (code "162") (name "unconnected-(GND-PadA5)") (class "Default")
      (node (ref "GND") (pin "A5") (pinfunction "A5_A5") (pintype "bidirectional"))
    )
    (net (code "163") (name "unconnected-(GND-PadAREF)") (class "Default")
      (node (ref "GND") (pin "AREF") (pinfunction "AREF_AREF") (pintype "bidirectional"))
    )
    (net (code "164") (name "unconnected-(GND-PadD12)") (class "Default")
      (node (ref "GND") (pin "D12") (pinfunction "D12_D12") (pintype "bidirectional"))
    )
    (net (code "165") (name "unconnected-(GND-PadD13)") (class "Default")
      (node (ref "GND") (pin "D13") (pinfunction "D13_D13") (pintype "bidirectional"))
    )
    (net (code "166") (name "unconnected-(GND-PadRX)") (class "Default")
      (node (ref "GND") (pin "RX") (pinfunction "RX_RX") (pintype "bidirectional"))
    )
    (net (code "167") (name "unconnected-(GND-PadTX)") (class "Default")
      (node (ref "GND") (pin "TX") (pinfunction "TX_TX") (pintype "bidirectional"))
    )
    (net (code "168") (name "unconnected-(IC1-O3-Pad16)") (class "Default")
      (node (ref "IC1") (pin "16") (pinfunction "O3_16") (pintype "open_collector"))
    )
    (net (code "169") (name "unconnected-(IC1-O4-Pad15)") (class "Default")
      (node (ref "IC1") (pin "15") (pinfunction "O4_15") (pintype "open_collector"))
    )
    (net (code "170") (name "unconnected-(IC1-O5-Pad14)") (class "Default")
      (node (ref "IC1") (pin "14") (pinfunction "O5_14") (pintype "open_collector"))
    )
    (net (code "171") (name "unconnected-(IC1-O6-Pad13)") (class "Default")
      (node (ref "IC1") (pin "13") (pinfunction "O6_13") (pintype "open_collector"))
    )
    (net (code "172") (name "unconnected-(IC1-O7-Pad12)") (class "Default")
      (node (ref "IC1") (pin "12") (pinfunction "O7_12") (pintype "open_collector"))
    )
    (net (code "173") (name "unconnected-(IC1-O8-Pad11)") (class "Default")
      (node (ref "IC1") (pin "11") (pinfunction "O8_11") (pintype "open_collector"))
    )
    (net (code "174") (name "unconnected-(IC2-GPA2-Pad23)") (class "Default")
      (node (ref "IC2") (pin "23") (pinfunction "GPA2_23") (pintype "bidirectional"))
    )
    (net (code "175") (name "unconnected-(IC2-GPA3-Pad24)") (class "Default")
      (node (ref "IC2") (pin "24") (pinfunction "GPA3_24") (pintype "bidirectional"))
    )
    (net (code "176") (name "unconnected-(IC2-GPA4-Pad25)") (class "Default")
      (node (ref "IC2") (pin "25") (pinfunction "GPA4_25") (pintype "bidirectional"))
    )
    (net (code "177") (name "unconnected-(IC2-GPA5-Pad26)") (class "Default")
      (node (ref "IC2") (pin "26") (pinfunction "GPA5_26") (pintype "bidirectional"))
    )
    (net (code "178") (name "unconnected-(IC2-GPA6-Pad27)") (class "Default")
      (node (ref "IC2") (pin "27") (pinfunction "GPA6_27") (pintype "bidirectional"))
    )
    (net (code "179") (name "unconnected-(IC2-GPA7-Pad28)") (class "Default")
      (node (ref "IC2") (pin "28") (pinfunction "GPA7_28") (pintype "bidirectional"))
    )
    (net (code "180") (name "unconnected-(IC2-INTA-Pad20)") (class "Default")
      (node (ref "IC2") (pin "20") (pinfunction "INTA_20") (pintype "output"))
    )
    (net (code "181") (name "unconnected-(IC2-INTB-Pad19)") (class "Default")
      (node (ref "IC2") (pin "19") (pinfunction "INTB_19") (pintype "output"))
    )
    (net (code "182") (name "unconnected-(IC4-INTA-Pad20)") (class "Default")
      (node (ref "IC4") (pin "20") (pinfunction "INTA_20") (pintype "output"))
    )
    (net (code "183") (name "unconnected-(IC4-INTB-Pad19)") (class "Default")
      (node (ref "IC4") (pin "19") (pinfunction "INTB_19") (pintype "output"))
    )
    (net (code "184") (name "unconnected-(IC5B-+IN-Pad5)") (class "Default")
      (node (ref "IC5") (pin "5") (pinfunction "+IN_5") (pintype "input"))
    )
    (net (code "185") (name "unconnected-(IC5B-OUT-Pad7)") (class "Default")
      (node (ref "IC5") (pin "7") (pinfunction "OUT_7") (pintype "output"))
    )
    (net (code "186") (name "unconnected-(JP1-Pad1)") (class "Default")
      (node (ref "JP1") (pin "1") (pinfunction "1_1") (pintype "passive"))
    )
    (net (code "187") (name "unconnected-(JP1-Pad2)") (class "Default")
      (node (ref "JP1") (pin "2") (pinfunction "2_2") (pintype "passive"))
    )
    (net (code "188") (name "unconnected-(JP2-Pad1)") (class "Default")
      (node (ref "JP2") (pin "1") (pinfunction "1_1") (pintype "passive"))
    )
    (net (code "189") (name "unconnected-(JP2-Pad2)") (class "Default")
      (node (ref "JP2") (pin "2") (pinfunction "2_2") (pintype "passive"))
    )
    (net (code "190") (name "unconnected-(JP2-Pad8)") (class "Default")
      (node (ref "JP2") (pin "8") (pinfunction "8_8") (pintype "passive"))
    )
    (net (code "191") (name "unconnected-(JP2-Pad9)") (class "Default")
      (node (ref "JP2") (pin "9") (pinfunction "9_9") (pintype "passive"))
    )
    (net (code "192") (name "unconnected-(JP2-Pad10)") (class "Default")
      (node (ref "JP2") (pin "10") (pinfunction "10_10") (pintype "passive"))
    )
    (net (code "193") (name "unconnected-(JP3-Pad2)") (class "Default")
      (node (ref "JP3") (pin "2") (pinfunction "2_2") (pintype "passive"))
    )
    (net (code "194") (name "unconnected-(JP3-Pad3)") (class "Default")
      (node (ref "JP3") (pin "3") (pinfunction "3_3") (pintype "passive"))
    )
    (net (code "195") (name "unconnected-(JP5-Pad2)") (class "Default")
      (node (ref "JP5") (pin "2") (pinfunction "2_2") (pintype "passive"))
    )
    (net (code "196") (name "unconnected-(JP5-Pad3)") (class "Default")
      (node (ref "JP5") (pin "3") (pinfunction "3_3") (pintype "passive"))
    )
    (net (code "197") (name "unconnected-(K1B-O-PadO1)") (class "Default")
      (node (ref "K1") (pin "O1") (pinfunction "O_O1") (pintype "passive"))
    )
    (net (code "198") (name "unconnected-(K1C-O-PadO2)") (class "Default")
      (node (ref "K1") (pin "O2") (pinfunction "O_O2") (pintype "passive"))
    )
    (net (code "199") (name "unconnected-(K1C-S-PadS2)") (class "Default")
      (node (ref "K1") (pin "S2") (pinfunction "S_S2") (pintype "passive"))
    )
    (net (code "200") (name "unconnected-(K2B-O-PadO1)") (class "Default")
      (node (ref "K2") (pin "O1") (pinfunction "O_O1") (pintype "passive"))
    )
    (net (code "201") (name "unconnected-(K2C-O-PadO2)") (class "Default")
      (node (ref "K2") (pin "O2") (pinfunction "O_O2") (pintype "passive"))
    )
    (net (code "202") (name "unconnected-(K2C-S-PadS2)") (class "Default")
      (node (ref "K2") (pin "S2") (pinfunction "S_S2") (pintype "passive"))
    )
  )
)
